# untitled.net
KiCad netlist of a schematic drawn in EAGLE
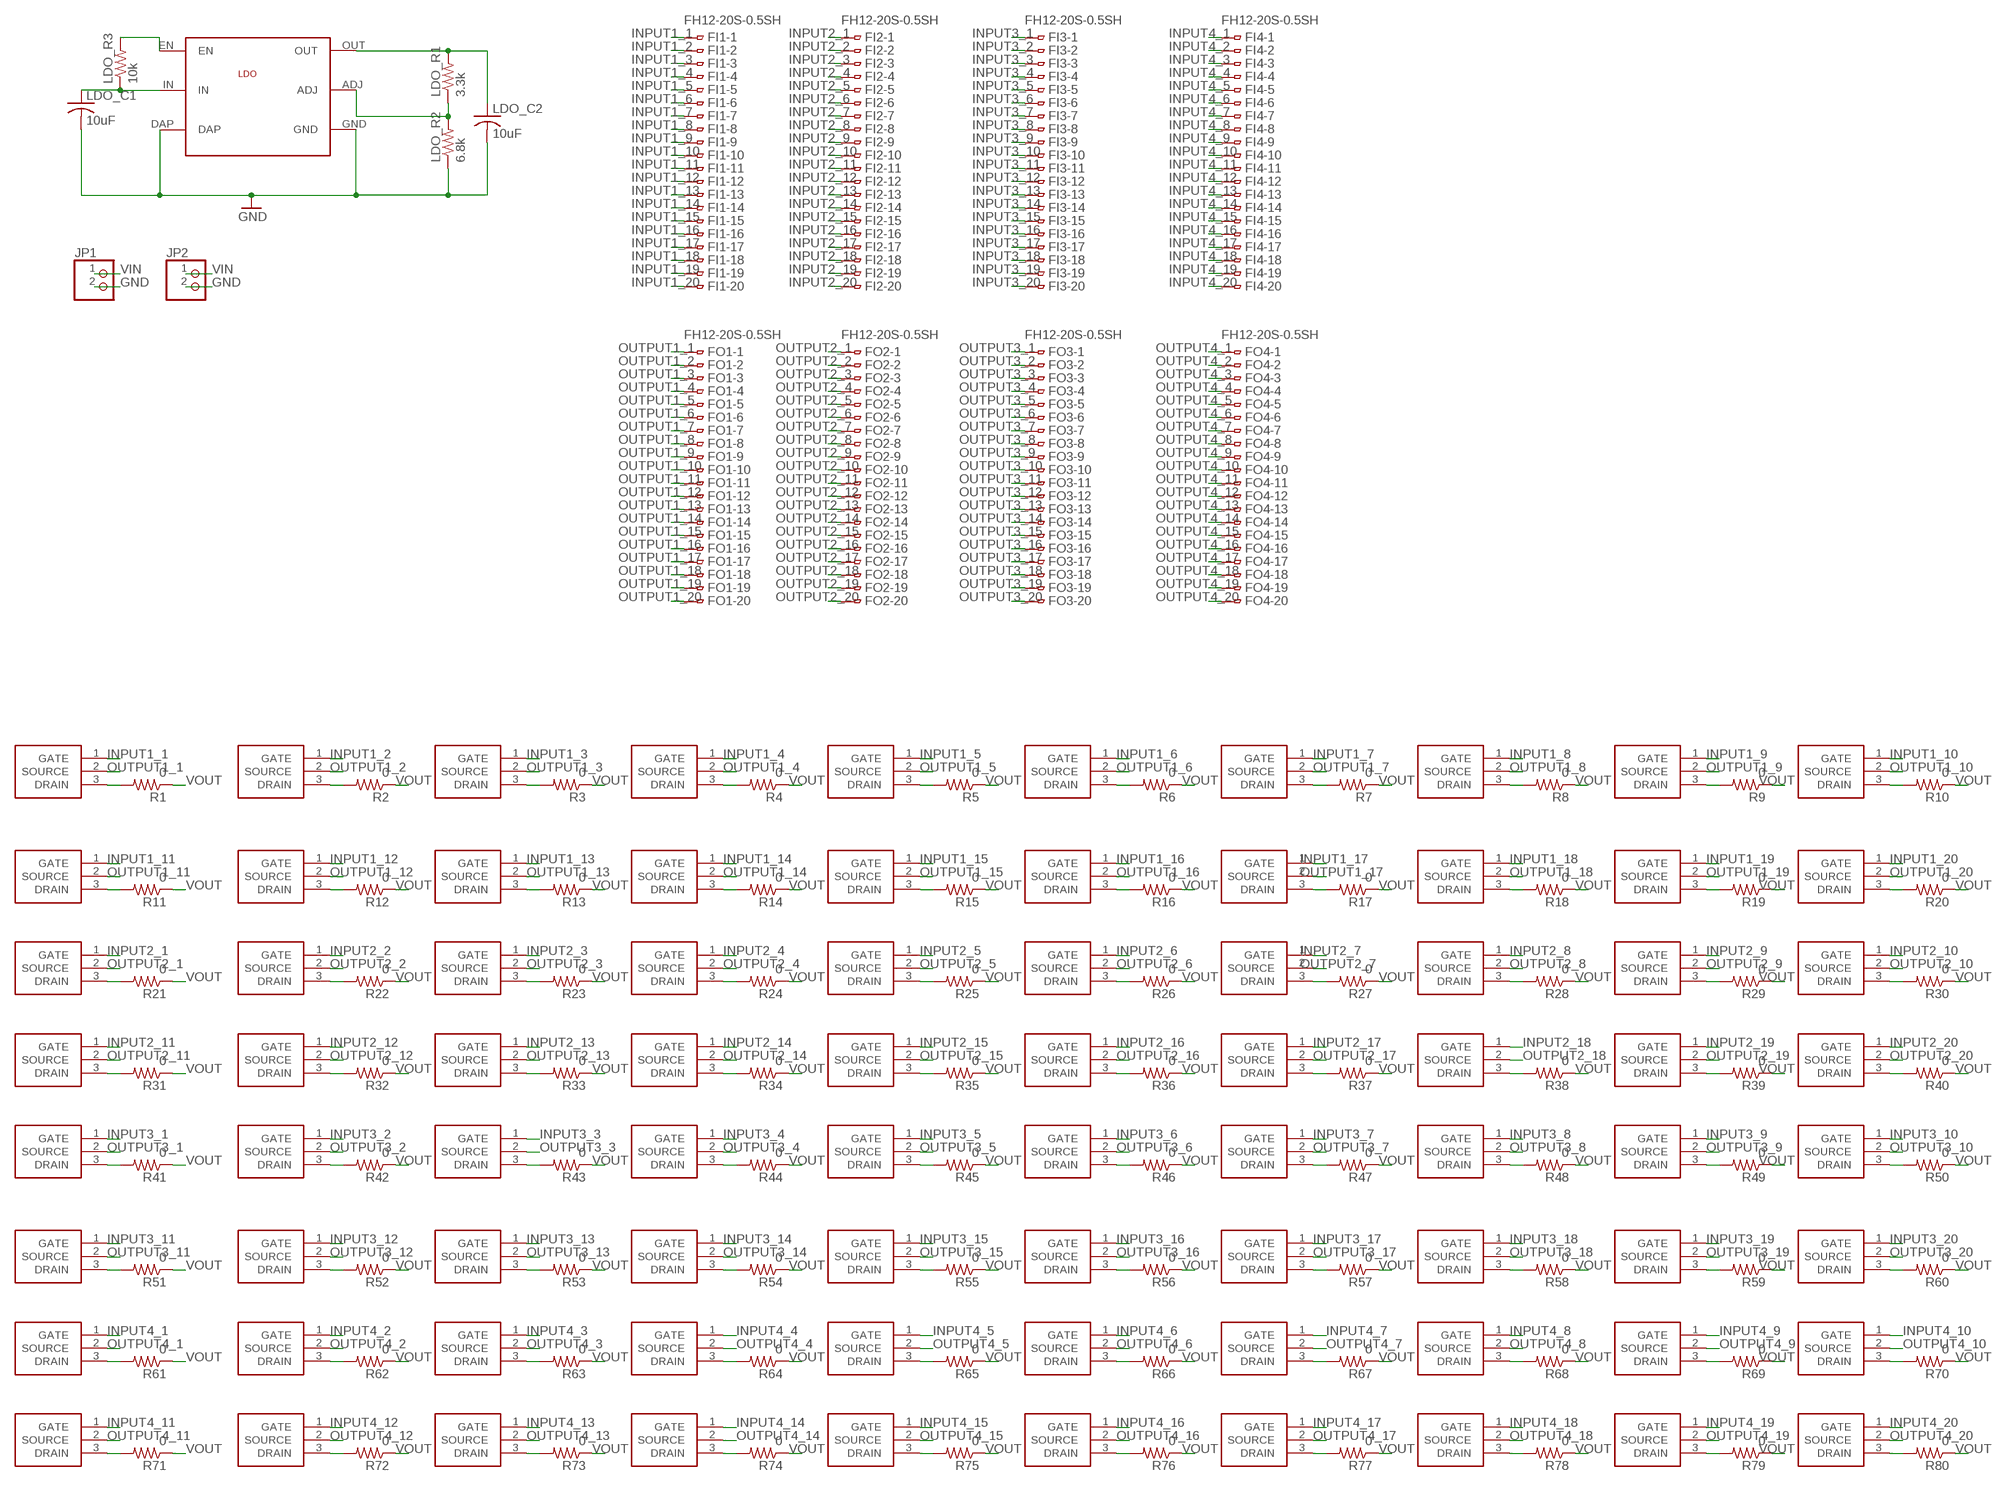
[diagram p0: schematic, sheet 1]

(export (version "E")
  (design (tool "Eeschema 10.0.6"))
  (components
    (comp (ref "FI1")
      (value "FH12-20S-0.5SH")
      (footprint "eagle-import:FH12-20S-0.5SH")
      (fields (field (name "MPN") "FH12-20S-0.5SH(55)"))
      (libsource (lib "eagle-import") (part "FH12-20S-0.5SH"))
    )
    (comp (ref "FI2")
      (value "FH12-20S-0.5SH")
      (footprint "eagle-import:FH12-20S-0.5SH")
      (fields (field (name "MPN") "FH12-20S-0.5SH(55)"))
      (libsource (lib "eagle-import") (part "FH12-20S-0.5SH"))
    )
    (comp (ref "FI3")
      (value "FH12-20S-0.5SH")
      (footprint "eagle-import:FH12-20S-0.5SH")
      (fields (field (name "MPN") "FH12-20S-0.5SH(55)"))
      (libsource (lib "eagle-import") (part "FH12-20S-0.5SH"))
    )
    (comp (ref "FI4")
      (value "FH12-20S-0.5SH")
      (footprint "eagle-import:FH12-20S-0.5SH")
      (fields (field (name "MPN") "FH12-20S-0.5SH(55)"))
      (libsource (lib "eagle-import") (part "FH12-20S-0.5SH"))
    )
    (comp (ref "FO1")
      (value "FH12-20S-0.5SH")
      (footprint "eagle-import:FH12-20S-0.5SH")
      (fields (field (name "MPN") "FH12-20S-0.5SH(55)"))
      (libsource (lib "eagle-import") (part "FH12-20S-0.5SH"))
    )
    (comp (ref "FO2")
      (value "FH12-20S-0.5SH")
      (footprint "eagle-import:FH12-20S-0.5SH")
      (fields (field (name "MPN") "FH12-20S-0.5SH(55)"))
      (libsource (lib "eagle-import") (part "FH12-20S-0.5SH"))
    )
    (comp (ref "FO3")
      (value "FH12-20S-0.5SH")
      (footprint "eagle-import:FH12-20S-0.5SH")
      (fields (field (name "MPN") "FH12-20S-0.5SH(55)"))
      (libsource (lib "eagle-import") (part "FH12-20S-0.5SH"))
    )
    (comp (ref "FO4")
      (value "FH12-20S-0.5SH")
      (footprint "eagle-import:FH12-20S-0.5SH")
      (fields (field (name "MPN") "FH12-20S-0.5SH(55)"))
      (libsource (lib "eagle-import") (part "FH12-20S-0.5SH"))
    )
    (comp (ref "JP1")
      (value "PINHD-1X2")
      (footprint "eagle-import:1X02")
      (libsource (lib "eagle-import") (part "PINHD-1X2"))
    )
    (comp (ref "JP2")
      (value "PINHD-1X2")
      (footprint "eagle-import:1X02")
      (libsource (lib "eagle-import") (part "PINHD-1X2"))
    )
    (comp (ref "LDO")
      (value "LP38501TS_ADJ")
      (footprint "eagle-import:LP38501TS_ADJ")
      (libsource (lib "eagle-import") (part "LP38501TS_ADJ"))
    )
    (comp (ref "LDO_C1")
      (value "10uF")
      (footprint "eagle-import:C0805")
      (libsource (lib "eagle-import") (part "C-USC0805"))
    )
    (comp (ref "LDO_C2")
      (value "10uF")
      (footprint "eagle-import:C0805")
      (libsource (lib "eagle-import") (part "C-USC0805"))
    )
    (comp (ref "LDO_R1")
      (value "3.3k")
      (footprint "eagle-import:R0805")
      (libsource (lib "eagle-import") (part "R-US_R0805"))
    )
    (comp (ref "LDO_R2")
      (value "6.8k")
      (footprint "eagle-import:R0805")
      (libsource (lib "eagle-import") (part "R-US_R0805"))
    )
    (comp (ref "LDO_R3")
      (value "10k")
      (footprint "eagle-import:R0805")
      (libsource (lib "eagle-import") (part "R-US_R0805"))
    )
    (comp (ref "MOS1")
      (value "NX6008NBKNX6008NBK")
      (footprint "eagle-import:SOT95P240X110-3N")
      (libsource (lib "eagle-import") (part "NX6008NBKNX6008NBK"))
    )
    (comp (ref "MOS2")
      (value "NX6008NBKNX6008NBK")
      (footprint "eagle-import:SOT95P240X110-3N")
      (libsource (lib "eagle-import") (part "NX6008NBKNX6008NBK"))
    )
    (comp (ref "MOS3")
      (value "NX6008NBKNX6008NBK")
      (footprint "eagle-import:SOT95P240X110-3N")
      (libsource (lib "eagle-import") (part "NX6008NBKNX6008NBK"))
    )
    (comp (ref "MOS4")
      (value "NX6008NBKNX6008NBK")
      (footprint "eagle-import:SOT95P240X110-3N")
      (libsource (lib "eagle-import") (part "NX6008NBKNX6008NBK"))
    )
    (comp (ref "MOS5")
      (value "NX6008NBKNX6008NBK")
      (footprint "eagle-import:SOT95P240X110-3N")
      (libsource (lib "eagle-import") (part "NX6008NBKNX6008NBK"))
    )
    (comp (ref "MOS6")
      (value "NX6008NBKNX6008NBK")
      (footprint "eagle-import:SOT95P240X110-3N")
      (libsource (lib "eagle-import") (part "NX6008NBKNX6008NBK"))
    )
    (comp (ref "MOS7")
      (value "NX6008NBKNX6008NBK")
      (footprint "eagle-import:SOT95P240X110-3N")
      (libsource (lib "eagle-import") (part "NX6008NBKNX6008NBK"))
    )
    (comp (ref "MOS8")
      (value "NX6008NBKNX6008NBK")
      (footprint "eagle-import:SOT95P240X110-3N")
      (libsource (lib "eagle-import") (part "NX6008NBKNX6008NBK"))
    )
    (comp (ref "MOS9")
      (value "NX6008NBKNX6008NBK")
      (footprint "eagle-import:SOT95P240X110-3N")
      (libsource (lib "eagle-import") (part "NX6008NBKNX6008NBK"))
    )
    (comp (ref "MOS10")
      (value "NX6008NBKNX6008NBK")
      (footprint "eagle-import:SOT95P240X110-3N")
      (libsource (lib "eagle-import") (part "NX6008NBKNX6008NBK"))
    )
    (comp (ref "MOS11")
      (value "NX6008NBKNX6008NBK")
      (footprint "eagle-import:SOT95P240X110-3N")
      (libsource (lib "eagle-import") (part "NX6008NBKNX6008NBK"))
    )
    (comp (ref "MOS12")
      (value "NX6008NBKNX6008NBK")
      (footprint "eagle-import:SOT95P240X110-3N")
      (libsource (lib "eagle-import") (part "NX6008NBKNX6008NBK"))
    )
    (comp (ref "MOS13")
      (value "NX6008NBKNX6008NBK")
      (footprint "eagle-import:SOT95P240X110-3N")
      (libsource (lib "eagle-import") (part "NX6008NBKNX6008NBK"))
    )
    (comp (ref "MOS14")
      (value "NX6008NBKNX6008NBK")
      (footprint "eagle-import:SOT95P240X110-3N")
      (libsource (lib "eagle-import") (part "NX6008NBKNX6008NBK"))
    )
    (comp (ref "MOS15")
      (value "NX6008NBKNX6008NBK")
      (footprint "eagle-import:SOT95P240X110-3N")
      (libsource (lib "eagle-import") (part "NX6008NBKNX6008NBK"))
    )
    (comp (ref "MOS16")
      (value "NX6008NBKNX6008NBK")
      (footprint "eagle-import:SOT95P240X110-3N")
      (libsource (lib "eagle-import") (part "NX6008NBKNX6008NBK"))
    )
    (comp (ref "MOS17")
      (value "NX6008NBKNX6008NBK")
      (footprint "eagle-import:SOT95P240X110-3N")
      (libsource (lib "eagle-import") (part "NX6008NBKNX6008NBK"))
    )
    (comp (ref "MOS18")
      (value "NX6008NBKNX6008NBK")
      (footprint "eagle-import:SOT95P240X110-3N")
      (libsource (lib "eagle-import") (part "NX6008NBKNX6008NBK"))
    )
    (comp (ref "MOS19")
      (value "NX6008NBKNX6008NBK")
      (footprint "eagle-import:SOT95P240X110-3N")
      (libsource (lib "eagle-import") (part "NX6008NBKNX6008NBK"))
    )
    (comp (ref "MOS20")
      (value "NX6008NBKNX6008NBK")
      (footprint "eagle-import:SOT95P240X110-3N")
      (libsource (lib "eagle-import") (part "NX6008NBKNX6008NBK"))
    )
    (comp (ref "MOS21")
      (value "NX6008NBKNX6008NBK")
      (footprint "eagle-import:SOT95P240X110-3N")
      (libsource (lib "eagle-import") (part "NX6008NBKNX6008NBK"))
    )
    (comp (ref "MOS22")
      (value "NX6008NBKNX6008NBK")
      (footprint "eagle-import:SOT95P240X110-3N")
      (libsource (lib "eagle-import") (part "NX6008NBKNX6008NBK"))
    )
    (comp (ref "MOS23")
      (value "NX6008NBKNX6008NBK")
      (footprint "eagle-import:SOT95P240X110-3N")
      (libsource (lib "eagle-import") (part "NX6008NBKNX6008NBK"))
    )
    (comp (ref "MOS24")
      (value "NX6008NBKNX6008NBK")
      (footprint "eagle-import:SOT95P240X110-3N")
      (libsource (lib "eagle-import") (part "NX6008NBKNX6008NBK"))
    )
    (comp (ref "MOS25")
      (value "NX6008NBKNX6008NBK")
      (footprint "eagle-import:SOT95P240X110-3N")
      (libsource (lib "eagle-import") (part "NX6008NBKNX6008NBK"))
    )
    (comp (ref "MOS26")
      (value "NX6008NBKNX6008NBK")
      (footprint "eagle-import:SOT95P240X110-3N")
      (libsource (lib "eagle-import") (part "NX6008NBKNX6008NBK"))
    )
    (comp (ref "MOS27")
      (value "NX6008NBKNX6008NBK")
      (footprint "eagle-import:SOT95P240X110-3N")
      (libsource (lib "eagle-import") (part "NX6008NBKNX6008NBK"))
    )
    (comp (ref "MOS28")
      (value "NX6008NBKNX6008NBK")
      (footprint "eagle-import:SOT95P240X110-3N")
      (libsource (lib "eagle-import") (part "NX6008NBKNX6008NBK"))
    )
    (comp (ref "MOS29")
      (value "NX6008NBKNX6008NBK")
      (footprint "eagle-import:SOT95P240X110-3N")
      (libsource (lib "eagle-import") (part "NX6008NBKNX6008NBK"))
    )
    (comp (ref "MOS30")
      (value "NX6008NBKNX6008NBK")
      (footprint "eagle-import:SOT95P240X110-3N")
      (libsource (lib "eagle-import") (part "NX6008NBKNX6008NBK"))
    )
    (comp (ref "MOS31")
      (value "NX6008NBKNX6008NBK")
      (footprint "eagle-import:SOT95P240X110-3N")
      (libsource (lib "eagle-import") (part "NX6008NBKNX6008NBK"))
    )
    (comp (ref "MOS32")
      (value "NX6008NBKNX6008NBK")
      (footprint "eagle-import:SOT95P240X110-3N")
      (libsource (lib "eagle-import") (part "NX6008NBKNX6008NBK"))
    )
    (comp (ref "MOS33")
      (value "NX6008NBKNX6008NBK")
      (footprint "eagle-import:SOT95P240X110-3N")
      (libsource (lib "eagle-import") (part "NX6008NBKNX6008NBK"))
    )
    (comp (ref "MOS34")
      (value "NX6008NBKNX6008NBK")
      (footprint "eagle-import:SOT95P240X110-3N")
      (libsource (lib "eagle-import") (part "NX6008NBKNX6008NBK"))
    )
    (comp (ref "MOS35")
      (value "NX6008NBKNX6008NBK")
      (footprint "eagle-import:SOT95P240X110-3N")
      (libsource (lib "eagle-import") (part "NX6008NBKNX6008NBK"))
    )
    (comp (ref "MOS36")
      (value "NX6008NBKNX6008NBK")
      (footprint "eagle-import:SOT95P240X110-3N")
      (libsource (lib "eagle-import") (part "NX6008NBKNX6008NBK"))
    )
    (comp (ref "MOS37")
      (value "NX6008NBKNX6008NBK")
      (footprint "eagle-import:SOT95P240X110-3N")
      (libsource (lib "eagle-import") (part "NX6008NBKNX6008NBK"))
    )
    (comp (ref "MOS38")
      (value "NX6008NBKNX6008NBK")
      (footprint "eagle-import:SOT95P240X110-3N")
      (libsource (lib "eagle-import") (part "NX6008NBKNX6008NBK"))
    )
    (comp (ref "MOS39")
      (value "NX6008NBKNX6008NBK")
      (footprint "eagle-import:SOT95P240X110-3N")
      (libsource (lib "eagle-import") (part "NX6008NBKNX6008NBK"))
    )
    (comp (ref "MOS40")
      (value "NX6008NBKNX6008NBK")
      (footprint "eagle-import:SOT95P240X110-3N")
      (libsource (lib "eagle-import") (part "NX6008NBKNX6008NBK"))
    )
    (comp (ref "MOS41")
      (value "NX6008NBKNX6008NBK")
      (footprint "eagle-import:SOT95P240X110-3N")
      (libsource (lib "eagle-import") (part "NX6008NBKNX6008NBK"))
    )
    (comp (ref "MOS42")
      (value "NX6008NBKNX6008NBK")
      (footprint "eagle-import:SOT95P240X110-3N")
      (libsource (lib "eagle-import") (part "NX6008NBKNX6008NBK"))
    )
    (comp (ref "MOS43")
      (value "NX6008NBKNX6008NBK")
      (footprint "eagle-import:SOT95P240X110-3N")
      (libsource (lib "eagle-import") (part "NX6008NBKNX6008NBK"))
    )
    (comp (ref "MOS44")
      (value "NX6008NBKNX6008NBK")
      (footprint "eagle-import:SOT95P240X110-3N")
      (libsource (lib "eagle-import") (part "NX6008NBKNX6008NBK"))
    )
    (comp (ref "MOS45")
      (value "NX6008NBKNX6008NBK")
      (footprint "eagle-import:SOT95P240X110-3N")
      (libsource (lib "eagle-import") (part "NX6008NBKNX6008NBK"))
    )
    (comp (ref "MOS46")
      (value "NX6008NBKNX6008NBK")
      (footprint "eagle-import:SOT95P240X110-3N")
      (libsource (lib "eagle-import") (part "NX6008NBKNX6008NBK"))
    )
    (comp (ref "MOS47")
      (value "NX6008NBKNX6008NBK")
      (footprint "eagle-import:SOT95P240X110-3N")
      (libsource (lib "eagle-import") (part "NX6008NBKNX6008NBK"))
    )
    (comp (ref "MOS48")
      (value "NX6008NBKNX6008NBK")
      (footprint "eagle-import:SOT95P240X110-3N")
      (libsource (lib "eagle-import") (part "NX6008NBKNX6008NBK"))
    )
    (comp (ref "MOS49")
      (value "NX6008NBKNX6008NBK")
      (footprint "eagle-import:SOT95P240X110-3N")
      (libsource (lib "eagle-import") (part "NX6008NBKNX6008NBK"))
    )
    (comp (ref "MOS50")
      (value "NX6008NBKNX6008NBK")
      (footprint "eagle-import:SOT95P240X110-3N")
      (libsource (lib "eagle-import") (part "NX6008NBKNX6008NBK"))
    )
    (comp (ref "MOS51")
      (value "NX6008NBKNX6008NBK")
      (footprint "eagle-import:SOT95P240X110-3N")
      (libsource (lib "eagle-import") (part "NX6008NBKNX6008NBK"))
    )
    (comp (ref "MOS52")
      (value "NX6008NBKNX6008NBK")
      (footprint "eagle-import:SOT95P240X110-3N")
      (libsource (lib "eagle-import") (part "NX6008NBKNX6008NBK"))
    )
    (comp (ref "MOS53")
      (value "NX6008NBKNX6008NBK")
      (footprint "eagle-import:SOT95P240X110-3N")
      (libsource (lib "eagle-import") (part "NX6008NBKNX6008NBK"))
    )
    (comp (ref "MOS54")
      (value "NX6008NBKNX6008NBK")
      (footprint "eagle-import:SOT95P240X110-3N")
      (libsource (lib "eagle-import") (part "NX6008NBKNX6008NBK"))
    )
    (comp (ref "MOS55")
      (value "NX6008NBKNX6008NBK")
      (footprint "eagle-import:SOT95P240X110-3N")
      (libsource (lib "eagle-import") (part "NX6008NBKNX6008NBK"))
    )
    (comp (ref "MOS56")
      (value "NX6008NBKNX6008NBK")
      (footprint "eagle-import:SOT95P240X110-3N")
      (libsource (lib "eagle-import") (part "NX6008NBKNX6008NBK"))
    )
    (comp (ref "MOS57")
      (value "NX6008NBKNX6008NBK")
      (footprint "eagle-import:SOT95P240X110-3N")
      (libsource (lib "eagle-import") (part "NX6008NBKNX6008NBK"))
    )
    (comp (ref "MOS58")
      (value "NX6008NBKNX6008NBK")
      (footprint "eagle-import:SOT95P240X110-3N")
      (libsource (lib "eagle-import") (part "NX6008NBKNX6008NBK"))
    )
    (comp (ref "MOS59")
      (value "NX6008NBKNX6008NBK")
      (footprint "eagle-import:SOT95P240X110-3N")
      (libsource (lib "eagle-import") (part "NX6008NBKNX6008NBK"))
    )
    (comp (ref "MOS60")
      (value "NX6008NBKNX6008NBK")
      (footprint "eagle-import:SOT95P240X110-3N")
      (libsource (lib "eagle-import") (part "NX6008NBKNX6008NBK"))
    )
    (comp (ref "MOS61")
      (value "NX6008NBKNX6008NBK")
      (footprint "eagle-import:SOT95P240X110-3N")
      (libsource (lib "eagle-import") (part "NX6008NBKNX6008NBK"))
    )
    (comp (ref "MOS62")
      (value "NX6008NBKNX6008NBK")
      (footprint "eagle-import:SOT95P240X110-3N")
      (libsource (lib "eagle-import") (part "NX6008NBKNX6008NBK"))
    )
    (comp (ref "MOS63")
      (value "NX6008NBKNX6008NBK")
      (footprint "eagle-import:SOT95P240X110-3N")
      (libsource (lib "eagle-import") (part "NX6008NBKNX6008NBK"))
    )
    (comp (ref "MOS64")
      (value "NX6008NBKNX6008NBK")
      (footprint "eagle-import:SOT95P240X110-3N")
      (libsource (lib "eagle-import") (part "NX6008NBKNX6008NBK"))
    )
    (comp (ref "MOS65")
      (value "NX6008NBKNX6008NBK")
      (footprint "eagle-import:SOT95P240X110-3N")
      (libsource (lib "eagle-import") (part "NX6008NBKNX6008NBK"))
    )
    (comp (ref "MOS66")
      (value "NX6008NBKNX6008NBK")
      (footprint "eagle-import:SOT95P240X110-3N")
      (libsource (lib "eagle-import") (part "NX6008NBKNX6008NBK"))
    )
    (comp (ref "MOS67")
      (value "NX6008NBKNX6008NBK")
      (footprint "eagle-import:SOT95P240X110-3N")
      (libsource (lib "eagle-import") (part "NX6008NBKNX6008NBK"))
    )
    (comp (ref "MOS68")
      (value "NX6008NBKNX6008NBK")
      (footprint "eagle-import:SOT95P240X110-3N")
      (libsource (lib "eagle-import") (part "NX6008NBKNX6008NBK"))
    )
    (comp (ref "MOS69")
      (value "NX6008NBKNX6008NBK")
      (footprint "eagle-import:SOT95P240X110-3N")
      (libsource (lib "eagle-import") (part "NX6008NBKNX6008NBK"))
    )
    (comp (ref "MOS70")
      (value "NX6008NBKNX6008NBK")
      (footprint "eagle-import:SOT95P240X110-3N")
      (libsource (lib "eagle-import") (part "NX6008NBKNX6008NBK"))
    )
    (comp (ref "MOS71")
      (value "NX6008NBKNX6008NBK")
      (footprint "eagle-import:SOT95P240X110-3N")
      (libsource (lib "eagle-import") (part "NX6008NBKNX6008NBK"))
    )
    (comp (ref "MOS72")
      (value "NX6008NBKNX6008NBK")
      (footprint "eagle-import:SOT95P240X110-3N")
      (libsource (lib "eagle-import") (part "NX6008NBKNX6008NBK"))
    )
    (comp (ref "MOS73")
      (value "NX6008NBKNX6008NBK")
      (footprint "eagle-import:SOT95P240X110-3N")
      (libsource (lib "eagle-import") (part "NX6008NBKNX6008NBK"))
    )
    (comp (ref "MOS74")
      (value "NX6008NBKNX6008NBK")
      (footprint "eagle-import:SOT95P240X110-3N")
      (libsource (lib "eagle-import") (part "NX6008NBKNX6008NBK"))
    )
    (comp (ref "MOS75")
      (value "NX6008NBKNX6008NBK")
      (footprint "eagle-import:SOT95P240X110-3N")
      (libsource (lib "eagle-import") (part "NX6008NBKNX6008NBK"))
    )
    (comp (ref "MOS76")
      (value "NX6008NBKNX6008NBK")
      (footprint "eagle-import:SOT95P240X110-3N")
      (libsource (lib "eagle-import") (part "NX6008NBKNX6008NBK"))
    )
    (comp (ref "MOS77")
      (value "NX6008NBKNX6008NBK")
      (footprint "eagle-import:SOT95P240X110-3N")
      (libsource (lib "eagle-import") (part "NX6008NBKNX6008NBK"))
    )
    (comp (ref "MOS78")
      (value "NX6008NBKNX6008NBK")
      (footprint "eagle-import:SOT95P240X110-3N")
      (libsource (lib "eagle-import") (part "NX6008NBKNX6008NBK"))
    )
    (comp (ref "MOS79")
      (value "NX6008NBKNX6008NBK")
      (footprint "eagle-import:SOT95P240X110-3N")
      (libsource (lib "eagle-import") (part "NX6008NBKNX6008NBK"))
    )
    (comp (ref "MOS80")
      (value "NX6008NBKNX6008NBK")
      (footprint "eagle-import:SOT95P240X110-3N")
      (libsource (lib "eagle-import") (part "NX6008NBKNX6008NBK"))
    )
    (comp (ref "R1")
      (value "0")
      (footprint "eagle-import:R0805")
      (libsource (lib "eagle-import") (part "R-US_R0805"))
    )
    (comp (ref "R2")
      (value "0")
      (footprint "eagle-import:R0805")
      (libsource (lib "eagle-import") (part "R-US_R0805"))
    )
    (comp (ref "R3")
      (value "0")
      (footprint "eagle-import:R0805")
      (libsource (lib "eagle-import") (part "R-US_R0805"))
    )
    (comp (ref "R4")
      (value "0")
      (footprint "eagle-import:R0805")
      (libsource (lib "eagle-import") (part "R-US_R0805"))
    )
    (comp (ref "R5")
      (value "0")
      (footprint "eagle-import:R0805")
      (libsource (lib "eagle-import") (part "R-US_R0805"))
    )
    (comp (ref "R6")
      (value "0")
      (footprint "eagle-import:R0805")
      (libsource (lib "eagle-import") (part "R-US_R0805"))
    )
    (comp (ref "R7")
      (value "0")
      (footprint "eagle-import:R0805")
      (libsource (lib "eagle-import") (part "R-US_R0805"))
    )
    (comp (ref "R8")
      (value "0")
      (footprint "eagle-import:R0805")
      (libsource (lib "eagle-import") (part "R-US_R0805"))
    )
    (comp (ref "R9")
      (value "0")
      (footprint "eagle-import:R0805")
      (libsource (lib "eagle-import") (part "R-US_R0805"))
    )
    (comp (ref "R10")
      (value "0")
      (footprint "eagle-import:R0805")
      (libsource (lib "eagle-import") (part "R-US_R0805"))
    )
    (comp (ref "R11")
      (value "0")
      (footprint "eagle-import:R0805")
      (libsource (lib "eagle-import") (part "R-US_R0805"))
    )
    (comp (ref "R12")
      (value "0")
      (footprint "eagle-import:R0805")
      (libsource (lib "eagle-import") (part "R-US_R0805"))
    )
    (comp (ref "R13")
      (value "0")
      (footprint "eagle-import:R0805")
      (libsource (lib "eagle-import") (part "R-US_R0805"))
    )
    (comp (ref "R14")
      (value "0")
      (footprint "eagle-import:R0805")
      (libsource (lib "eagle-import") (part "R-US_R0805"))
    )
    (comp (ref "R15")
      (value "0")
      (footprint "eagle-import:R0805")
      (libsource (lib "eagle-import") (part "R-US_R0805"))
    )
    (comp (ref "R16")
      (value "0")
      (footprint "eagle-import:R0805")
      (libsource (lib "eagle-import") (part "R-US_R0805"))
    )
    (comp (ref "R17")
      (value "0")
      (footprint "eagle-import:R0805")
      (libsource (lib "eagle-import") (part "R-US_R0805"))
    )
    (comp (ref "R18")
      (value "0")
      (footprint "eagle-import:R0805")
      (libsource (lib "eagle-import") (part "R-US_R0805"))
    )
    (comp (ref "R19")
      (value "0")
      (footprint "eagle-import:R0805")
      (libsource (lib "eagle-import") (part "R-US_R0805"))
    )
    (comp (ref "R20")
      (value "0")
      (footprint "eagle-import:R0805")
      (libsource (lib "eagle-import") (part "R-US_R0805"))
    )
    (comp (ref "R21")
      (value "0")
      (footprint "eagle-import:R0805")
      (libsource (lib "eagle-import") (part "R-US_R0805"))
    )
    (comp (ref "R22")
      (value "0")
      (footprint "eagle-import:R0805")
      (libsource (lib "eagle-import") (part "R-US_R0805"))
    )
    (comp (ref "R23")
      (value "0")
      (footprint "eagle-import:R0805")
      (libsource (lib "eagle-import") (part "R-US_R0805"))
    )
    (comp (ref "R24")
      (value "0")
      (footprint "eagle-import:R0805")
      (libsource (lib "eagle-import") (part "R-US_R0805"))
    )
    (comp (ref "R25")
      (value "0")
      (footprint "eagle-import:R0805")
      (libsource (lib "eagle-import") (part "R-US_R0805"))
    )
    (comp (ref "R26")
      (value "0")
      (footprint "eagle-import:R0805")
      (libsource (lib "eagle-import") (part "R-US_R0805"))
    )
    (comp (ref "R27")
      (value "0")
      (footprint "eagle-import:R0805")
      (libsource (lib "eagle-import") (part "R-US_R0805"))
    )
    (comp (ref "R28")
      (value "0")
      (footprint "eagle-import:R0805")
      (libsource (lib "eagle-import") (part "R-US_R0805"))
    )
    (comp (ref "R29")
      (value "0")
      (footprint "eagle-import:R0805")
      (libsource (lib "eagle-import") (part "R-US_R0805"))
    )
    (comp (ref "R30")
      (value "0")
      (footprint "eagle-import:R0805")
      (libsource (lib "eagle-import") (part "R-US_R0805"))
    )
    (comp (ref "R31")
      (value "0")
      (footprint "eagle-import:R0805")
      (libsource (lib "eagle-import") (part "R-US_R0805"))
    )
    (comp (ref "R32")
      (value "0")
      (footprint "eagle-import:R0805")
      (libsource (lib "eagle-import") (part "R-US_R0805"))
    )
    (comp (ref "R33")
      (value "0")
      (footprint "eagle-import:R0805")
      (libsource (lib "eagle-import") (part "R-US_R0805"))
    )
    (comp (ref "R34")
      (value "0")
      (footprint "eagle-import:R0805")
      (libsource (lib "eagle-import") (part "R-US_R0805"))
    )
    (comp (ref "R35")
      (value "0")
      (footprint "eagle-import:R0805")
      (libsource (lib "eagle-import") (part "R-US_R0805"))
    )
    (comp (ref "R36")
      (value "0")
      (footprint "eagle-import:R0805")
      (libsource (lib "eagle-import") (part "R-US_R0805"))
    )
    (comp (ref "R37")
      (value "0")
      (footprint "eagle-import:R0805")
      (libsource (lib "eagle-import") (part "R-US_R0805"))
    )
    (comp (ref "R38")
      (value "0")
      (footprint "eagle-import:R0805")
      (libsource (lib "eagle-import") (part "R-US_R0805"))
    )
    (comp (ref "R39")
      (value "0")
      (footprint "eagle-import:R0805")
      (libsource (lib "eagle-import") (part "R-US_R0805"))
    )
    (comp (ref "R40")
      (value "0")
      (footprint "eagle-import:R0805")
      (libsource (lib "eagle-import") (part "R-US_R0805"))
    )
    (comp (ref "R41")
      (value "0")
      (footprint "eagle-import:R0805")
      (libsource (lib "eagle-import") (part "R-US_R0805"))
    )
    (comp (ref "R42")
      (value "0")
      (footprint "eagle-import:R0805")
      (libsource (lib "eagle-import") (part "R-US_R0805"))
    )
    (comp (ref "R43")
      (value "0")
      (footprint "eagle-import:R0805")
      (libsource (lib "eagle-import") (part "R-US_R0805"))
    )
    (comp (ref "R44")
      (value "0")
      (footprint "eagle-import:R0805")
      (libsource (lib "eagle-import") (part "R-US_R0805"))
    )
    (comp (ref "R45")
      (value "0")
      (footprint "eagle-import:R0805")
      (libsource (lib "eagle-import") (part "R-US_R0805"))
    )
    (comp (ref "R46")
      (value "0")
      (footprint "eagle-import:R0805")
      (libsource (lib "eagle-import") (part "R-US_R0805"))
    )
    (comp (ref "R47")
      (value "0")
      (footprint "eagle-import:R0805")
      (libsource (lib "eagle-import") (part "R-US_R0805"))
    )
    (comp (ref "R48")
      (value "0")
      (footprint "eagle-import:R0805")
      (libsource (lib "eagle-import") (part "R-US_R0805"))
    )
    (comp (ref "R49")
      (value "0")
      (footprint "eagle-import:R0805")
      (libsource (lib "eagle-import") (part "R-US_R0805"))
    )
    (comp (ref "R50")
      (value "0")
      (footprint "eagle-import:R0805")
      (libsource (lib "eagle-import") (part "R-US_R0805"))
    )
    (comp (ref "R51")
      (value "0")
      (footprint "eagle-import:R0805")
      (libsource (lib "eagle-import") (part "R-US_R0805"))
    )
    (comp (ref "R52")
      (value "0")
      (footprint "eagle-import:R0805")
      (libsource (lib "eagle-import") (part "R-US_R0805"))
    )
    (comp (ref "R53")
      (value "0")
      (footprint "eagle-import:R0805")
      (libsource (lib "eagle-import") (part "R-US_R0805"))
    )
    (comp (ref "R54")
      (value "0")
      (footprint "eagle-import:R0805")
      (libsource (lib "eagle-import") (part "R-US_R0805"))
    )
    (comp (ref "R55")
      (value "0")
      (footprint "eagle-import:R0805")
      (libsource (lib "eagle-import") (part "R-US_R0805"))
    )
    (comp (ref "R56")
      (value "0")
      (footprint "eagle-import:R0805")
      (libsource (lib "eagle-import") (part "R-US_R0805"))
    )
    (comp (ref "R57")
      (value "0")
      (footprint "eagle-import:R0805")
      (libsource (lib "eagle-import") (part "R-US_R0805"))
    )
    (comp (ref "R58")
      (value "0")
      (footprint "eagle-import:R0805")
      (libsource (lib "eagle-import") (part "R-US_R0805"))
    )
    (comp (ref "R59")
      (value "0")
      (footprint "eagle-import:R0805")
      (libsource (lib "eagle-import") (part "R-US_R0805"))
    )
    (comp (ref "R60")
      (value "0")
      (footprint "eagle-import:R0805")
      (libsource (lib "eagle-import") (part "R-US_R0805"))
    )
    (comp (ref "R61")
      (value "0")
      (footprint "eagle-import:R0805")
      (libsource (lib "eagle-import") (part "R-US_R0805"))
    )
    (comp (ref "R62")
      (value "0")
      (footprint "eagle-import:R0805")
      (libsource (lib "eagle-import") (part "R-US_R0805"))
    )
    (comp (ref "R63")
      (value "0")
      (footprint "eagle-import:R0805")
      (libsource (lib "eagle-import") (part "R-US_R0805"))
    )
    (comp (ref "R64")
      (value "0")
      (footprint "eagle-import:R0805")
      (libsource (lib "eagle-import") (part "R-US_R0805"))
    )
    (comp (ref "R65")
      (value "0")
      (footprint "eagle-import:R0805")
      (libsource (lib "eagle-import") (part "R-US_R0805"))
    )
    (comp (ref "R66")
      (value "0")
      (footprint "eagle-import:R0805")
      (libsource (lib "eagle-import") (part "R-US_R0805"))
    )
    (comp (ref "R67")
      (value "0")
      (footprint "eagle-import:R0805")
      (libsource (lib "eagle-import") (part "R-US_R0805"))
    )
    (comp (ref "R68")
      (value "0")
      (footprint "eagle-import:R0805")
      (libsource (lib "eagle-import") (part "R-US_R0805"))
    )
    (comp (ref "R69")
      (value "0")
      (footprint "eagle-import:R0805")
      (libsource (lib "eagle-import") (part "R-US_R0805"))
    )
    (comp (ref "R70")
      (value "0")
      (footprint "eagle-import:R0805")
      (libsource (lib "eagle-import") (part "R-US_R0805"))
    )
    (comp (ref "R71")
      (value "0")
      (footprint "eagle-import:R0805")
      (libsource (lib "eagle-import") (part "R-US_R0805"))
    )
    (comp (ref "R72")
      (value "0")
      (footprint "eagle-import:R0805")
      (libsource (lib "eagle-import") (part "R-US_R0805"))
    )
    (comp (ref "R73")
      (value "0")
      (footprint "eagle-import:R0805")
      (libsource (lib "eagle-import") (part "R-US_R0805"))
    )
    (comp (ref "R74")
      (value "0")
      (footprint "eagle-import:R0805")
      (libsource (lib "eagle-import") (part "R-US_R0805"))
    )
    (comp (ref "R75")
      (value "0")
      (footprint "eagle-import:R0805")
      (libsource (lib "eagle-import") (part "R-US_R0805"))
    )
    (comp (ref "R76")
      (value "0")
      (footprint "eagle-import:R0805")
      (libsource (lib "eagle-import") (part "R-US_R0805"))
    )
    (comp (ref "R77")
      (value "0")
      (footprint "eagle-import:R0805")
      (libsource (lib "eagle-import") (part "R-US_R0805"))
    )
    (comp (ref "R78")
      (value "0")
      (footprint "eagle-import:R0805")
      (libsource (lib "eagle-import") (part "R-US_R0805"))
    )
    (comp (ref "R79")
      (value "0")
      (footprint "eagle-import:R0805")
      (libsource (lib "eagle-import") (part "R-US_R0805"))
    )
    (comp (ref "R80")
      (value "0")
      (footprint "eagle-import:R0805")
      (libsource (lib "eagle-import") (part "R-US_R0805"))
    )
  )
  (nets
    (net (code "1") (name "/INPUT1_1") (class "Default")
      (node (ref "FI1") (pin "1") (pinfunction "1_1") (pintype "passive"))
      (node (ref "MOS1") (pin "1") (pinfunction "GATE_1") (pintype "bidirectional"))
    )
    (net (code "2") (name "/INPUT1_2") (class "Default")
      (node (ref "FI1") (pin "2") (pinfunction "1_2") (pintype "passive"))
      (node (ref "MOS2") (pin "1") (pinfunction "GATE_1") (pintype "bidirectional"))
    )
    (net (code "3") (name "/INPUT1_3") (class "Default")
      (node (ref "FI1") (pin "3") (pinfunction "1_3") (pintype "passive"))
      (node (ref "MOS3") (pin "1") (pinfunction "GATE_1") (pintype "bidirectional"))
    )
    (net (code "4") (name "/INPUT1_4") (class "Default")
      (node (ref "FI1") (pin "4") (pinfunction "1_4") (pintype "passive"))
      (node (ref "MOS4") (pin "1") (pinfunction "GATE_1") (pintype "bidirectional"))
    )
    (net (code "5") (name "/INPUT1_5") (class "Default")
      (node (ref "FI1") (pin "5") (pinfunction "1_5") (pintype "passive"))
      (node (ref "MOS5") (pin "1") (pinfunction "GATE_1") (pintype "bidirectional"))
    )
    (net (code "6") (name "/INPUT1_6") (class "Default")
      (node (ref "FI1") (pin "6") (pinfunction "1_6") (pintype "passive"))
      (node (ref "MOS6") (pin "1") (pinfunction "GATE_1") (pintype "bidirectional"))
    )
    (net (code "7") (name "/INPUT1_7") (class "Default")
      (node (ref "FI1") (pin "7") (pinfunction "1_7") (pintype "passive"))
      (node (ref "MOS7") (pin "1") (pinfunction "GATE_1") (pintype "bidirectional"))
    )
    (net (code "8") (name "/INPUT1_8") (class "Default")
      (node (ref "FI1") (pin "8") (pinfunction "1_8") (pintype "passive"))
      (node (ref "MOS8") (pin "1") (pinfunction "GATE_1") (pintype "bidirectional"))
    )
    (net (code "9") (name "/INPUT1_9") (class "Default")
      (node (ref "FI1") (pin "9") (pinfunction "1_9") (pintype "passive"))
      (node (ref "MOS9") (pin "1") (pinfunction "GATE_1") (pintype "bidirectional"))
    )
    (net (code "10") (name "/INPUT1_10") (class "Default")
      (node (ref "FI1") (pin "10") (pinfunction "1_10") (pintype "passive"))
      (node (ref "MOS10") (pin "1") (pinfunction "GATE_1") (pintype "bidirectional"))
    )
    (net (code "11") (name "/INPUT1_11") (class "Default")
      (node (ref "FI1") (pin "11") (pinfunction "1_11") (pintype "passive"))
      (node (ref "MOS11") (pin "1") (pinfunction "GATE_1") (pintype "bidirectional"))
    )
    (net (code "12") (name "/INPUT1_12") (class "Default")
      (node (ref "FI1") (pin "12") (pinfunction "1_12") (pintype "passive"))
      (node (ref "MOS12") (pin "1") (pinfunction "GATE_1") (pintype "bidirectional"))
    )
    (net (code "13") (name "/INPUT1_13") (class "Default")
      (node (ref "FI1") (pin "13") (pinfunction "1_13") (pintype "passive"))
      (node (ref "MOS13") (pin "1") (pinfunction "GATE_1") (pintype "bidirectional"))
    )
    (net (code "14") (name "/INPUT1_14") (class "Default")
      (node (ref "FI1") (pin "14") (pinfunction "1_14") (pintype "passive"))
      (node (ref "MOS14") (pin "1") (pinfunction "GATE_1") (pintype "bidirectional"))
    )
    (net (code "15") (name "/INPUT1_15") (class "Default")
      (node (ref "FI1") (pin "15") (pinfunction "1_15") (pintype "passive"))
      (node (ref "MOS15") (pin "1") (pinfunction "GATE_1") (pintype "bidirectional"))
    )
    (net (code "16") (name "/INPUT1_16") (class "Default")
      (node (ref "FI1") (pin "16") (pinfunction "1_16") (pintype "passive"))
      (node (ref "MOS16") (pin "1") (pinfunction "GATE_1") (pintype "bidirectional"))
    )
    (net (code "17") (name "/INPUT1_17") (class "Default")
      (node (ref "FI1") (pin "17") (pinfunction "1_17") (pintype "passive"))
      (node (ref "MOS17") (pin "1") (pinfunction "GATE_1") (pintype "bidirectional"))
    )
    (net (code "18") (name "/INPUT1_18") (class "Default")
      (node (ref "FI1") (pin "18") (pinfunction "1_18") (pintype "passive"))
      (node (ref "MOS18") (pin "1") (pinfunction "GATE_1") (pintype "bidirectional"))
    )
    (net (code "19") (name "/INPUT1_19") (class "Default")
      (node (ref "FI1") (pin "19") (pinfunction "1_19") (pintype "passive"))
      (node (ref "MOS19") (pin "1") (pinfunction "GATE_1") (pintype "bidirectional"))
    )
    (net (code "20") (name "/INPUT1_20") (class "Default")
      (node (ref "FI1") (pin "20") (pinfunction "1_20") (pintype "passive"))
      (node (ref "MOS20") (pin "1") (pinfunction "GATE_1") (pintype "bidirectional"))
    )
    (net (code "21") (name "/INPUT2_1") (class "Default")
      (node (ref "FI2") (pin "1") (pinfunction "1_1") (pintype "passive"))
      (node (ref "MOS21") (pin "1") (pinfunction "GATE_1") (pintype "bidirectional"))
    )
    (net (code "22") (name "/INPUT2_2") (class "Default")
      (node (ref "FI2") (pin "2") (pinfunction "1_2") (pintype "passive"))
      (node (ref "MOS22") (pin "1") (pinfunction "GATE_1") (pintype "bidirectional"))
    )
    (net (code "23") (name "/INPUT2_3") (class "Default")
      (node (ref "FI2") (pin "3") (pinfunction "1_3") (pintype "passive"))
      (node (ref "MOS23") (pin "1") (pinfunction "GATE_1") (pintype "bidirectional"))
    )
    (net (code "24") (name "/INPUT2_4") (class "Default")
      (node (ref "FI2") (pin "4") (pinfunction "1_4") (pintype "passive"))
      (node (ref "MOS24") (pin "1") (pinfunction "GATE_1") (pintype "bidirectional"))
    )
    (net (code "25") (name "/INPUT2_5") (class "Default")
      (node (ref "FI2") (pin "5") (pinfunction "1_5") (pintype "passive"))
      (node (ref "MOS25") (pin "1") (pinfunction "GATE_1") (pintype "bidirectional"))
    )
    (net (code "26") (name "/INPUT2_6") (class "Default")
      (node (ref "FI2") (pin "6") (pinfunction "1_6") (pintype "passive"))
      (node (ref "MOS26") (pin "1") (pinfunction "GATE_1") (pintype "bidirectional"))
    )
    (net (code "27") (name "/INPUT2_7") (class "Default")
      (node (ref "FI2") (pin "7") (pinfunction "1_7") (pintype "passive"))
      (node (ref "MOS27") (pin "1") (pinfunction "GATE_1") (pintype "bidirectional"))
    )
    (net (code "28") (name "/INPUT2_8") (class "Default")
      (node (ref "FI2") (pin "8") (pinfunction "1_8") (pintype "passive"))
      (node (ref "MOS28") (pin "1") (pinfunction "GATE_1") (pintype "bidirectional"))
    )
    (net (code "29") (name "/INPUT2_9") (class "Default")
      (node (ref "FI2") (pin "9") (pinfunction "1_9") (pintype "passive"))
      (node (ref "MOS29") (pin "1") (pinfunction "GATE_1") (pintype "bidirectional"))
    )
    (net (code "30") (name "/INPUT2_10") (class "Default")
      (node (ref "FI2") (pin "10") (pinfunction "1_10") (pintype "passive"))
      (node (ref "MOS30") (pin "1") (pinfunction "GATE_1") (pintype "bidirectional"))
    )
    (net (code "31") (name "/INPUT2_11") (class "Default")
      (node (ref "FI2") (pin "11") (pinfunction "1_11") (pintype "passive"))
      (node (ref "MOS31") (pin "1") (pinfunction "GATE_1") (pintype "bidirectional"))
    )
    (net (code "32") (name "/INPUT2_12") (class "Default")
      (node (ref "FI2") (pin "12") (pinfunction "1_12") (pintype "passive"))
      (node (ref "MOS32") (pin "1") (pinfunction "GATE_1") (pintype "bidirectional"))
    )
    (net (code "33") (name "/INPUT2_13") (class "Default")
      (node (ref "FI2") (pin "13") (pinfunction "1_13") (pintype "passive"))
      (node (ref "MOS33") (pin "1") (pinfunction "GATE_1") (pintype "bidirectional"))
    )
    (net (code "34") (name "/INPUT2_14") (class "Default")
      (node (ref "FI2") (pin "14") (pinfunction "1_14") (pintype "passive"))
      (node (ref "MOS34") (pin "1") (pinfunction "GATE_1") (pintype "bidirectional"))
    )
    (net (code "35") (name "/INPUT2_15") (class "Default")
      (node (ref "FI2") (pin "15") (pinfunction "1_15") (pintype "passive"))
      (node (ref "MOS35") (pin "1") (pinfunction "GATE_1") (pintype "bidirectional"))
    )
    (net (code "36") (name "/INPUT2_16") (class "Default")
      (node (ref "FI2") (pin "16") (pinfunction "1_16") (pintype "passive"))
      (node (ref "MOS36") (pin "1") (pinfunction "GATE_1") (pintype "bidirectional"))
    )
    (net (code "37") (name "/INPUT2_17") (class "Default")
      (node (ref "FI2") (pin "17") (pinfunction "1_17") (pintype "passive"))
      (node (ref "MOS37") (pin "1") (pinfunction "GATE_1") (pintype "bidirectional"))
    )
    (net (code "38") (name "/INPUT2_18") (class "Default")
      (node (ref "FI2") (pin "18") (pinfunction "1_18") (pintype "passive"))
      (node (ref "MOS38") (pin "1") (pinfunction "GATE_1") (pintype "bidirectional"))
    )
    (net (code "39") (name "/INPUT2_19") (class "Default")
      (node (ref "FI2") (pin "19") (pinfunction "1_19") (pintype "passive"))
      (node (ref "MOS39") (pin "1") (pinfunction "GATE_1") (pintype "bidirectional"))
    )
    (net (code "40") (name "/INPUT2_20") (class "Default")
      (node (ref "FI2") (pin "20") (pinfunction "1_20") (pintype "passive"))
      (node (ref "MOS40") (pin "1") (pinfunction "GATE_1") (pintype "bidirectional"))
    )
    (net (code "41") (name "/INPUT3_1") (class "Default")
      (node (ref "FI3") (pin "1") (pinfunction "1_1") (pintype "passive"))
      (node (ref "MOS41") (pin "1") (pinfunction "GATE_1") (pintype "bidirectional"))
    )
    (net (code "42") (name "/INPUT3_2") (class "Default")
      (node (ref "FI3") (pin "2") (pinfunction "1_2") (pintype "passive"))
      (node (ref "MOS42") (pin "1") (pinfunction "GATE_1") (pintype "bidirectional"))
    )
    (net (code "43") (name "/INPUT3_3") (class "Default")
      (node (ref "FI3") (pin "3") (pinfunction "1_3") (pintype "passive"))
      (node (ref "MOS43") (pin "1") (pinfunction "GATE_1") (pintype "bidirectional"))
    )
    (net (code "44") (name "/INPUT3_4") (class "Default")
      (node (ref "FI3") (pin "4") (pinfunction "1_4") (pintype "passive"))
      (node (ref "MOS44") (pin "1") (pinfunction "GATE_1") (pintype "bidirectional"))
    )
    (net (code "45") (name "/INPUT3_5") (class "Default")
      (node (ref "FI3") (pin "5") (pinfunction "1_5") (pintype "passive"))
      (node (ref "MOS45") (pin "1") (pinfunction "GATE_1") (pintype "bidirectional"))
    )
    (net (code "46") (name "/INPUT3_6") (class "Default")
      (node (ref "FI3") (pin "6") (pinfunction "1_6") (pintype "passive"))
      (node (ref "MOS46") (pin "1") (pinfunction "GATE_1") (pintype "bidirectional"))
    )
    (net (code "47") (name "/INPUT3_7") (class "Default")
      (node (ref "FI3") (pin "7") (pinfunction "1_7") (pintype "passive"))
      (node (ref "MOS47") (pin "1") (pinfunction "GATE_1") (pintype "bidirectional"))
    )
    (net (code "48") (name "/INPUT3_8") (class "Default")
      (node (ref "FI3") (pin "8") (pinfunction "1_8") (pintype "passive"))
      (node (ref "MOS48") (pin "1") (pinfunction "GATE_1") (pintype "bidirectional"))
    )
    (net (code "49") (name "/INPUT3_9") (class "Default")
      (node (ref "FI3") (pin "9") (pinfunction "1_9") (pintype "passive"))
      (node (ref "MOS49") (pin "1") (pinfunction "GATE_1") (pintype "bidirectional"))
    )
    (net (code "50") (name "/INPUT3_10") (class "Default")
      (node (ref "FI3") (pin "10") (pinfunction "1_10") (pintype "passive"))
      (node (ref "MOS50") (pin "1") (pinfunction "GATE_1") (pintype "bidirectional"))
    )
    (net (code "51") (name "/INPUT3_11") (class "Default")
      (node (ref "FI3") (pin "11") (pinfunction "1_11") (pintype "passive"))
      (node (ref "MOS51") (pin "1") (pinfunction "GATE_1") (pintype "bidirectional"))
    )
    (net (code "52") (name "/INPUT3_12") (class "Default")
      (node (ref "FI3") (pin "12") (pinfunction "1_12") (pintype "passive"))
      (node (ref "MOS52") (pin "1") (pinfunction "GATE_1") (pintype "bidirectional"))
    )
    (net (code "53") (name "/INPUT3_13") (class "Default")
      (node (ref "FI3") (pin "13") (pinfunction "1_13") (pintype "passive"))
      (node (ref "MOS53") (pin "1") (pinfunction "GATE_1") (pintype "bidirectional"))
    )
    (net (code "54") (name "/INPUT3_14") (class "Default")
      (node (ref "FI3") (pin "14") (pinfunction "1_14") (pintype "passive"))
      (node (ref "MOS54") (pin "1") (pinfunction "GATE_1") (pintype "bidirectional"))
    )
    (net (code "55") (name "/INPUT3_15") (class "Default")
      (node (ref "FI3") (pin "15") (pinfunction "1_15") (pintype "passive"))
      (node (ref "MOS55") (pin "1") (pinfunction "GATE_1") (pintype "bidirectional"))
    )
    (net (code "56") (name "/INPUT3_16") (class "Default")
      (node (ref "FI3") (pin "16") (pinfunction "1_16") (pintype "passive"))
      (node (ref "MOS56") (pin "1") (pinfunction "GATE_1") (pintype "bidirectional"))
    )
    (net (code "57") (name "/INPUT3_17") (class "Default")
      (node (ref "FI3") (pin "17") (pinfunction "1_17") (pintype "passive"))
      (node (ref "MOS57") (pin "1") (pinfunction "GATE_1") (pintype "bidirectional"))
    )
    (net (code "58") (name "/INPUT3_18") (class "Default")
      (node (ref "FI3") (pin "18") (pinfunction "1_18") (pintype "passive"))
      (node (ref "MOS58") (pin "1") (pinfunction "GATE_1") (pintype "bidirectional"))
    )
    (net (code "59") (name "/INPUT3_19") (class "Default")
      (node (ref "FI3") (pin "19") (pinfunction "1_19") (pintype "passive"))
      (node (ref "MOS59") (pin "1") (pinfunction "GATE_1") (pintype "bidirectional"))
    )
    (net (code "60") (name "/INPUT3_20") (class "Default")
      (node (ref "FI3") (pin "20") (pinfunction "1_20") (pintype "passive"))
      (node (ref "MOS60") (pin "1") (pinfunction "GATE_1") (pintype "bidirectional"))
    )
    (net (code "61") (name "/INPUT4_1") (class "Default")
      (node (ref "FI4") (pin "1") (pinfunction "1_1") (pintype "passive"))
      (node (ref "MOS61") (pin "1") (pinfunction "GATE_1") (pintype "bidirectional"))
    )
    (net (code "62") (name "/INPUT4_2") (class "Default")
      (node (ref "FI4") (pin "2") (pinfunction "1_2") (pintype "passive"))
      (node (ref "MOS62") (pin "1") (pinfunction "GATE_1") (pintype "bidirectional"))
    )
    (net (code "63") (name "/INPUT4_3") (class "Default")
      (node (ref "FI4") (pin "3") (pinfunction "1_3") (pintype "passive"))
      (node (ref "MOS63") (pin "1") (pinfunction "GATE_1") (pintype "bidirectional"))
    )
    (net (code "64") (name "/INPUT4_4") (class "Default")
      (node (ref "FI4") (pin "4") (pinfunction "1_4") (pintype "passive"))
      (node (ref "MOS64") (pin "1") (pinfunction "GATE_1") (pintype "bidirectional"))
    )
    (net (code "65") (name "/INPUT4_5") (class "Default")
      (node (ref "FI4") (pin "5") (pinfunction "1_5") (pintype "passive"))
      (node (ref "MOS65") (pin "1") (pinfunction "GATE_1") (pintype "bidirectional"))
    )
    (net (code "66") (name "/INPUT4_6") (class "Default")
      (node (ref "FI4") (pin "6") (pinfunction "1_6") (pintype "passive"))
      (node (ref "MOS66") (pin "1") (pinfunction "GATE_1") (pintype "bidirectional"))
    )
    (net (code "67") (name "/INPUT4_7") (class "Default")
      (node (ref "FI4") (pin "7") (pinfunction "1_7") (pintype "passive"))
      (node (ref "MOS67") (pin "1") (pinfunction "GATE_1") (pintype "bidirectional"))
    )
    (net (code "68") (name "/INPUT4_8") (class "Default")
      (node (ref "FI4") (pin "8") (pinfunction "1_8") (pintype "passive"))
      (node (ref "MOS68") (pin "1") (pinfunction "GATE_1") (pintype "bidirectional"))
    )
    (net (code "69") (name "/INPUT4_9") (class "Default")
      (node (ref "FI4") (pin "9") (pinfunction "1_9") (pintype "passive"))
      (node (ref "MOS69") (pin "1") (pinfunction "GATE_1") (pintype "bidirectional"))
    )
    (net (code "70") (name "/INPUT4_10") (class "Default")
      (node (ref "FI4") (pin "10") (pinfunction "1_10") (pintype "passive"))
      (node (ref "MOS70") (pin "1") (pinfunction "GATE_1") (pintype "bidirectional"))
    )
    (net (code "71") (name "/INPUT4_11") (class "Default")
      (node (ref "FI4") (pin "11") (pinfunction "1_11") (pintype "passive"))
      (node (ref "MOS71") (pin "1") (pinfunction "GATE_1") (pintype "bidirectional"))
    )
    (net (code "72") (name "/INPUT4_12") (class "Default")
      (node (ref "FI4") (pin "12") (pinfunction "1_12") (pintype "passive"))
      (node (ref "MOS72") (pin "1") (pinfunction "GATE_1") (pintype "bidirectional"))
    )
    (net (code "73") (name "/INPUT4_13") (class "Default")
      (node (ref "FI4") (pin "13") (pinfunction "1_13") (pintype "passive"))
      (node (ref "MOS73") (pin "1") (pinfunction "GATE_1") (pintype "bidirectional"))
    )
    (net (code "74") (name "/INPUT4_14") (class "Default")
      (node (ref "FI4") (pin "14") (pinfunction "1_14") (pintype "passive"))
      (node (ref "MOS74") (pin "1") (pinfunction "GATE_1") (pintype "bidirectional"))
    )
    (net (code "75") (name "/INPUT4_15") (class "Default")
      (node (ref "FI4") (pin "15") (pinfunction "1_15") (pintype "passive"))
      (node (ref "MOS75") (pin "1") (pinfunction "GATE_1") (pintype "bidirectional"))
    )
    (net (code "76") (name "/INPUT4_16") (class "Default")
      (node (ref "FI4") (pin "16") (pinfunction "1_16") (pintype "passive"))
      (node (ref "MOS76") (pin "1") (pinfunction "GATE_1") (pintype "bidirectional"))
    )
    (net (code "77") (name "/INPUT4_17") (class "Default")
      (node (ref "FI4") (pin "17") (pinfunction "1_17") (pintype "passive"))
      (node (ref "MOS77") (pin "1") (pinfunction "GATE_1") (pintype "bidirectional"))
    )
    (net (code "78") (name "/INPUT4_18") (class "Default")
      (node (ref "FI4") (pin "18") (pinfunction "1_18") (pintype "passive"))
      (node (ref "MOS78") (pin "1") (pinfunction "GATE_1") (pintype "bidirectional"))
    )
    (net (code "79") (name "/INPUT4_19") (class "Default")
      (node (ref "FI4") (pin "19") (pinfunction "1_19") (pintype "passive"))
      (node (ref "MOS79") (pin "1") (pinfunction "GATE_1") (pintype "bidirectional"))
    )
    (net (code "80") (name "/INPUT4_20") (class "Default")
      (node (ref "FI4") (pin "20") (pinfunction "1_20") (pintype "passive"))
      (node (ref "MOS80") (pin "1") (pinfunction "GATE_1") (pintype "bidirectional"))
    )
    (net (code "81") (name "/OUTPUT1_1") (class "Default")
      (node (ref "FO1") (pin "1") (pinfunction "1_1") (pintype "passive"))
      (node (ref "MOS1") (pin "2") (pinfunction "SOURCE_2") (pintype "bidirectional"))
    )
    (net (code "82") (name "/OUTPUT1_2") (class "Default")
      (node (ref "FO1") (pin "2") (pinfunction "1_2") (pintype "passive"))
      (node (ref "MOS2") (pin "2") (pinfunction "SOURCE_2") (pintype "bidirectional"))
    )
    (net (code "83") (name "/OUTPUT1_3") (class "Default")
      (node (ref "FO1") (pin "3") (pinfunction "1_3") (pintype "passive"))
      (node (ref "MOS3") (pin "2") (pinfunction "SOURCE_2") (pintype "bidirectional"))
    )
    (net (code "84") (name "/OUTPUT1_4") (class "Default")
      (node (ref "FO1") (pin "4") (pinfunction "1_4") (pintype "passive"))
      (node (ref "MOS4") (pin "2") (pinfunction "SOURCE_2") (pintype "bidirectional"))
    )
    (net (code "85") (name "/OUTPUT1_5") (class "Default")
      (node (ref "FO1") (pin "5") (pinfunction "1_5") (pintype "passive"))
      (node (ref "MOS5") (pin "2") (pinfunction "SOURCE_2") (pintype "bidirectional"))
    )
    (net (code "86") (name "/OUTPUT1_6") (class "Default")
      (node (ref "FO1") (pin "6") (pinfunction "1_6") (pintype "passive"))
      (node (ref "MOS6") (pin "2") (pinfunction "SOURCE_2") (pintype "bidirectional"))
    )
    (net (code "87") (name "/OUTPUT1_7") (class "Default")
      (node (ref "FO1") (pin "7") (pinfunction "1_7") (pintype "passive"))
      (node (ref "MOS7") (pin "2") (pinfunction "SOURCE_2") (pintype "bidirectional"))
    )
    (net (code "88") (name "/OUTPUT1_8") (class "Default")
      (node (ref "FO1") (pin "8") (pinfunction "1_8") (pintype "passive"))
      (node (ref "MOS8") (pin "2") (pinfunction "SOURCE_2") (pintype "bidirectional"))
    )
    (net (code "89") (name "/OUTPUT1_9") (class "Default")
      (node (ref "FO1") (pin "9") (pinfunction "1_9") (pintype "passive"))
      (node (ref "MOS9") (pin "2") (pinfunction "SOURCE_2") (pintype "bidirectional"))
    )
    (net (code "90") (name "/OUTPUT1_10") (class "Default")
      (node (ref "FO1") (pin "10") (pinfunction "1_10") (pintype "passive"))
      (node (ref "MOS10") (pin "2") (pinfunction "SOURCE_2") (pintype "bidirectional"))
    )
    (net (code "91") (name "/OUTPUT1_11") (class "Default")
      (node (ref "FO1") (pin "11") (pinfunction "1_11") (pintype "passive"))
      (node (ref "MOS11") (pin "2") (pinfunction "SOURCE_2") (pintype "bidirectional"))
    )
    (net (code "92") (name "/OUTPUT1_12") (class "Default")
      (node (ref "FO1") (pin "12") (pinfunction "1_12") (pintype "passive"))
      (node (ref "MOS12") (pin "2") (pinfunction "SOURCE_2") (pintype "bidirectional"))
    )
    (net (code "93") (name "/OUTPUT1_13") (class "Default")
      (node (ref "FO1") (pin "13") (pinfunction "1_13") (pintype "passive"))
      (node (ref "MOS13") (pin "2") (pinfunction "SOURCE_2") (pintype "bidirectional"))
    )
    (net (code "94") (name "/OUTPUT1_14") (class "Default")
      (node (ref "FO1") (pin "14") (pinfunction "1_14") (pintype "passive"))
      (node (ref "MOS14") (pin "2") (pinfunction "SOURCE_2") (pintype "bidirectional"))
    )
    (net (code "95") (name "/OUTPUT1_15") (class "Default")
      (node (ref "FO1") (pin "15") (pinfunction "1_15") (pintype "passive"))
      (node (ref "MOS15") (pin "2") (pinfunction "SOURCE_2") (pintype "bidirectional"))
    )
    (net (code "96") (name "/OUTPUT1_16") (class "Default")
      (node (ref "FO1") (pin "16") (pinfunction "1_16") (pintype "passive"))
      (node (ref "MOS16") (pin "2") (pinfunction "SOURCE_2") (pintype "bidirectional"))
    )
    (net (code "97") (name "/OUTPUT1_17") (class "Default")
      (node (ref "FO1") (pin "17") (pinfunction "1_17") (pintype "passive"))
      (node (ref "MOS17") (pin "2") (pinfunction "SOURCE_2") (pintype "bidirectional"))
    )
    (net (code "98") (name "/OUTPUT1_18") (class "Default")
      (node (ref "FO1") (pin "18") (pinfunction "1_18") (pintype "passive"))
      (node (ref "MOS18") (pin "2") (pinfunction "SOURCE_2") (pintype "bidirectional"))
    )
    (net (code "99") (name "/OUTPUT1_19") (class "Default")
      (node (ref "FO1") (pin "19") (pinfunction "1_19") (pintype "passive"))
      (node (ref "MOS19") (pin "2") (pinfunction "SOURCE_2") (pintype "bidirectional"))
    )
    (net (code "100") (name "/OUTPUT1_20") (class "Default")
      (node (ref "FO1") (pin "20") (pinfunction "1_20") (pintype "passive"))
      (node (ref "MOS20") (pin "2") (pinfunction "SOURCE_2") (pintype "bidirectional"))
    )
    (net (code "101") (name "/OUTPUT2_1") (class "Default")
      (node (ref "FO2") (pin "1") (pinfunction "1_1") (pintype "passive"))
      (node (ref "MOS21") (pin "2") (pinfunction "SOURCE_2") (pintype "bidirectional"))
    )
    (net (code "102") (name "/OUTPUT2_2") (class "Default")
      (node (ref "FO2") (pin "2") (pinfunction "1_2") (pintype "passive"))
      (node (ref "MOS22") (pin "2") (pinfunction "SOURCE_2") (pintype "bidirectional"))
    )
    (net (code "103") (name "/OUTPUT2_3") (class "Default")
      (node (ref "FO2") (pin "3") (pinfunction "1_3") (pintype "passive"))
      (node (ref "MOS23") (pin "2") (pinfunction "SOURCE_2") (pintype "bidirectional"))
    )
    (net (code "104") (name "/OUTPUT2_4") (class "Default")
      (node (ref "FO2") (pin "4") (pinfunction "1_4") (pintype "passive"))
      (node (ref "MOS24") (pin "2") (pinfunction "SOURCE_2") (pintype "bidirectional"))
    )
    (net (code "105") (name "/OUTPUT2_5") (class "Default")
      (node (ref "FO2") (pin "5") (pinfunction "1_5") (pintype "passive"))
      (node (ref "MOS25") (pin "2") (pinfunction "SOURCE_2") (pintype "bidirectional"))
    )
    (net (code "106") (name "/OUTPUT2_6") (class "Default")
      (node (ref "FO2") (pin "6") (pinfunction "1_6") (pintype "passive"))
      (node (ref "MOS26") (pin "2") (pinfunction "SOURCE_2") (pintype "bidirectional"))
    )
    (net (code "107") (name "/OUTPUT2_7") (class "Default")
      (node (ref "FO2") (pin "7") (pinfunction "1_7") (pintype "passive"))
      (node (ref "MOS27") (pin "2") (pinfunction "SOURCE_2") (pintype "bidirectional"))
    )
    (net (code "108") (name "/OUTPUT2_8") (class "Default")
      (node (ref "FO2") (pin "8") (pinfunction "1_8") (pintype "passive"))
      (node (ref "MOS28") (pin "2") (pinfunction "SOURCE_2") (pintype "bidirectional"))
    )
    (net (code "109") (name "/OUTPUT2_9") (class "Default")
      (node (ref "FO2") (pin "9") (pinfunction "1_9") (pintype "passive"))
      (node (ref "MOS29") (pin "2") (pinfunction "SOURCE_2") (pintype "bidirectional"))
    )
    (net (code "110") (name "/OUTPUT2_10") (class "Default")
      (node (ref "FO2") (pin "10") (pinfunction "1_10") (pintype "passive"))
      (node (ref "MOS30") (pin "2") (pinfunction "SOURCE_2") (pintype "bidirectional"))
    )
    (net (code "111") (name "/OUTPUT2_11") (class "Default")
      (node (ref "FO2") (pin "11") (pinfunction "1_11") (pintype "passive"))
      (node (ref "MOS31") (pin "2") (pinfunction "SOURCE_2") (pintype "bidirectional"))
    )
    (net (code "112") (name "/OUTPUT2_12") (class "Default")
      (node (ref "FO2") (pin "12") (pinfunction "1_12") (pintype "passive"))
      (node (ref "MOS32") (pin "2") (pinfunction "SOURCE_2") (pintype "bidirectional"))
    )
    (net (code "113") (name "/OUTPUT2_13") (class "Default")
      (node (ref "FO2") (pin "13") (pinfunction "1_13") (pintype "passive"))
      (node (ref "MOS33") (pin "2") (pinfunction "SOURCE_2") (pintype "bidirectional"))
    )
    (net (code "114") (name "/OUTPUT2_14") (class "Default")
      (node (ref "FO2") (pin "14") (pinfunction "1_14") (pintype "passive"))
      (node (ref "MOS34") (pin "2") (pinfunction "SOURCE_2") (pintype "bidirectional"))
    )
    (net (code "115") (name "/OUTPUT2_15") (class "Default")
      (node (ref "FO2") (pin "15") (pinfunction "1_15") (pintype "passive"))
      (node (ref "MOS35") (pin "2") (pinfunction "SOURCE_2") (pintype "bidirectional"))
    )
    (net (code "116") (name "/OUTPUT2_16") (class "Default")
      (node (ref "FO2") (pin "16") (pinfunction "1_16") (pintype "passive"))
      (node (ref "MOS36") (pin "2") (pinfunction "SOURCE_2") (pintype "bidirectional"))
    )
    (net (code "117") (name "/OUTPUT2_17") (class "Default")
      (node (ref "FO2") (pin "17") (pinfunction "1_17") (pintype "passive"))
      (node (ref "MOS37") (pin "2") (pinfunction "SOURCE_2") (pintype "bidirectional"))
    )
    (net (code "118") (name "/OUTPUT2_18") (class "Default")
      (node (ref "FO2") (pin "18") (pinfunction "1_18") (pintype "passive"))
      (node (ref "MOS38") (pin "2") (pinfunction "SOURCE_2") (pintype "bidirectional"))
    )
    (net (code "119") (name "/OUTPUT2_19") (class "Default")
      (node (ref "FO2") (pin "19") (pinfunction "1_19") (pintype "passive"))
      (node (ref "MOS39") (pin "2") (pinfunction "SOURCE_2") (pintype "bidirectional"))
    )
    (net (code "120") (name "/OUTPUT2_20") (class "Default")
      (node (ref "FO2") (pin "20") (pinfunction "1_20") (pintype "passive"))
      (node (ref "MOS40") (pin "2") (pinfunction "SOURCE_2") (pintype "bidirectional"))
    )
    (net (code "121") (name "/OUTPUT3_1") (class "Default")
      (node (ref "FO3") (pin "1") (pinfunction "1_1") (pintype "passive"))
      (node (ref "MOS41") (pin "2") (pinfunction "SOURCE_2") (pintype "bidirectional"))
    )
    (net (code "122") (name "/OUTPUT3_2") (class "Default")
      (node (ref "FO3") (pin "2") (pinfunction "1_2") (pintype "passive"))
      (node (ref "MOS42") (pin "2") (pinfunction "SOURCE_2") (pintype "bidirectional"))
    )
    (net (code "123") (name "/OUTPUT3_3") (class "Default")
      (node (ref "FO3") (pin "3") (pinfunction "1_3") (pintype "passive"))
      (node (ref "MOS43") (pin "2") (pinfunction "SOURCE_2") (pintype "bidirectional"))
    )
    (net (code "124") (name "/OUTPUT3_4") (class "Default")
      (node (ref "FO3") (pin "4") (pinfunction "1_4") (pintype "passive"))
      (node (ref "MOS44") (pin "2") (pinfunction "SOURCE_2") (pintype "bidirectional"))
    )
    (net (code "125") (name "/OUTPUT3_5") (class "Default")
      (node (ref "FO3") (pin "5") (pinfunction "1_5") (pintype "passive"))
      (node (ref "MOS45") (pin "2") (pinfunction "SOURCE_2") (pintype "bidirectional"))
    )
    (net (code "126") (name "/OUTPUT3_6") (class "Default")
      (node (ref "FO3") (pin "6") (pinfunction "1_6") (pintype "passive"))
      (node (ref "MOS46") (pin "2") (pinfunction "SOURCE_2") (pintype "bidirectional"))
    )
    (net (code "127") (name "/OUTPUT3_7") (class "Default")
      (node (ref "FO3") (pin "7") (pinfunction "1_7") (pintype "passive"))
      (node (ref "MOS47") (pin "2") (pinfunction "SOURCE_2") (pintype "bidirectional"))
    )
    (net (code "128") (name "/OUTPUT3_8") (class "Default")
      (node (ref "FO3") (pin "8") (pinfunction "1_8") (pintype "passive"))
      (node (ref "MOS48") (pin "2") (pinfunction "SOURCE_2") (pintype "bidirectional"))
    )
    (net (code "129") (name "/OUTPUT3_9") (class "Default")
      (node (ref "FO3") (pin "9") (pinfunction "1_9") (pintype "passive"))
      (node (ref "MOS49") (pin "2") (pinfunction "SOURCE_2") (pintype "bidirectional"))
    )
    (net (code "130") (name "/OUTPUT3_10") (class "Default")
      (node (ref "FO3") (pin "10") (pinfunction "1_10") (pintype "passive"))
      (node (ref "MOS50") (pin "2") (pinfunction "SOURCE_2") (pintype "bidirectional"))
    )
    (net (code "131") (name "/OUTPUT3_11") (class "Default")
      (node (ref "FO3") (pin "11") (pinfunction "1_11") (pintype "passive"))
      (node (ref "MOS51") (pin "2") (pinfunction "SOURCE_2") (pintype "bidirectional"))
    )
    (net (code "132") (name "/OUTPUT3_12") (class "Default")
      (node (ref "FO3") (pin "12") (pinfunction "1_12") (pintype "passive"))
      (node (ref "MOS52") (pin "2") (pinfunction "SOURCE_2") (pintype "bidirectional"))
    )
    (net (code "133") (name "/OUTPUT3_13") (class "Default")
      (node (ref "FO3") (pin "13") (pinfunction "1_13") (pintype "passive"))
      (node (ref "MOS53") (pin "2") (pinfunction "SOURCE_2") (pintype "bidirectional"))
    )
    (net (code "134") (name "/OUTPUT3_14") (class "Default")
      (node (ref "FO3") (pin "14") (pinfunction "1_14") (pintype "passive"))
      (node (ref "MOS54") (pin "2") (pinfunction "SOURCE_2") (pintype "bidirectional"))
    )
    (net (code "135") (name "/OUTPUT3_15") (class "Default")
      (node (ref "FO3") (pin "15") (pinfunction "1_15") (pintype "passive"))
      (node (ref "MOS55") (pin "2") (pinfunction "SOURCE_2") (pintype "bidirectional"))
    )
    (net (code "136") (name "/OUTPUT3_16") (class "Default")
      (node (ref "FO3") (pin "16") (pinfunction "1_16") (pintype "passive"))
      (node (ref "MOS56") (pin "2") (pinfunction "SOURCE_2") (pintype "bidirectional"))
    )
    (net (code "137") (name "/OUTPUT3_17") (class "Default")
      (node (ref "FO3") (pin "17") (pinfunction "1_17") (pintype "passive"))
      (node (ref "MOS57") (pin "2") (pinfunction "SOURCE_2") (pintype "bidirectional"))
    )
    (net (code "138") (name "/OUTPUT3_18") (class "Default")
      (node (ref "FO3") (pin "18") (pinfunction "1_18") (pintype "passive"))
      (node (ref "MOS58") (pin "2") (pinfunction "SOURCE_2") (pintype "bidirectional"))
    )
    (net (code "139") (name "/OUTPUT3_19") (class "Default")
      (node (ref "FO3") (pin "19") (pinfunction "1_19") (pintype "passive"))
      (node (ref "MOS59") (pin "2") (pinfunction "SOURCE_2") (pintype "bidirectional"))
    )
    (net (code "140") (name "/OUTPUT3_20") (class "Default")
      (node (ref "FO3") (pin "20") (pinfunction "1_20") (pintype "passive"))
      (node (ref "MOS60") (pin "2") (pinfunction "SOURCE_2") (pintype "bidirectional"))
    )
    (net (code "141") (name "/OUTPUT4_1") (class "Default")
      (node (ref "FO4") (pin "1") (pinfunction "1_1") (pintype "passive"))
      (node (ref "MOS61") (pin "2") (pinfunction "SOURCE_2") (pintype "bidirectional"))
    )
    (net (code "142") (name "/OUTPUT4_2") (class "Default")
      (node (ref "FO4") (pin "2") (pinfunction "1_2") (pintype "passive"))
      (node (ref "MOS62") (pin "2") (pinfunction "SOURCE_2") (pintype "bidirectional"))
    )
    (net (code "143") (name "/OUTPUT4_3") (class "Default")
      (node (ref "FO4") (pin "3") (pinfunction "1_3") (pintype "passive"))
      (node (ref "MOS63") (pin "2") (pinfunction "SOURCE_2") (pintype "bidirectional"))
    )
    (net (code "144") (name "/OUTPUT4_4") (class "Default")
      (node (ref "FO4") (pin "4") (pinfunction "1_4") (pintype "passive"))
      (node (ref "MOS64") (pin "2") (pinfunction "SOURCE_2") (pintype "bidirectional"))
    )
    (net (code "145") (name "/OUTPUT4_5") (class "Default")
      (node (ref "FO4") (pin "5") (pinfunction "1_5") (pintype "passive"))
      (node (ref "MOS65") (pin "2") (pinfunction "SOURCE_2") (pintype "bidirectional"))
    )
    (net (code "146") (name "/OUTPUT4_6") (class "Default")
      (node (ref "FO4") (pin "6") (pinfunction "1_6") (pintype "passive"))
      (node (ref "MOS66") (pin "2") (pinfunction "SOURCE_2") (pintype "bidirectional"))
    )
    (net (code "147") (name "/OUTPUT4_7") (class "Default")
      (node (ref "FO4") (pin "7") (pinfunction "1_7") (pintype "passive"))
      (node (ref "MOS67") (pin "2") (pinfunction "SOURCE_2") (pintype "bidirectional"))
    )
    (net (code "148") (name "/OUTPUT4_8") (class "Default")
      (node (ref "FO4") (pin "8") (pinfunction "1_8") (pintype "passive"))
      (node (ref "MOS68") (pin "2") (pinfunction "SOURCE_2") (pintype "bidirectional"))
    )
    (net (code "149") (name "/OUTPUT4_9") (class "Default")
      (node (ref "FO4") (pin "9") (pinfunction "1_9") (pintype "passive"))
      (node (ref "MOS69") (pin "2") (pinfunction "SOURCE_2") (pintype "bidirectional"))
    )
    (net (code "150") (name "/OUTPUT4_10") (class "Default")
      (node (ref "FO4") (pin "10") (pinfunction "1_10") (pintype "passive"))
      (node (ref "MOS70") (pin "2") (pinfunction "SOURCE_2") (pintype "bidirectional"))
    )
    (net (code "151") (name "/OUTPUT4_11") (class "Default")
      (node (ref "FO4") (pin "11") (pinfunction "1_11") (pintype "passive"))
      (node (ref "MOS71") (pin "2") (pinfunction "SOURCE_2") (pintype "bidirectional"))
    )
    (net (code "152") (name "/OUTPUT4_12") (class "Default")
      (node (ref "FO4") (pin "12") (pinfunction "1_12") (pintype "passive"))
      (node (ref "MOS72") (pin "2") (pinfunction "SOURCE_2") (pintype "bidirectional"))
    )
    (net (code "153") (name "/OUTPUT4_13") (class "Default")
      (node (ref "FO4") (pin "13") (pinfunction "1_13") (pintype "passive"))
      (node (ref "MOS73") (pin "2") (pinfunction "SOURCE_2") (pintype "bidirectional"))
    )
    (net (code "154") (name "/OUTPUT4_14") (class "Default")
      (node (ref "FO4") (pin "14") (pinfunction "1_14") (pintype "passive"))
      (node (ref "MOS74") (pin "2") (pinfunction "SOURCE_2") (pintype "bidirectional"))
    )
    (net (code "155") (name "/OUTPUT4_15") (class "Default")
      (node (ref "FO4") (pin "15") (pinfunction "1_15") (pintype "passive"))
      (node (ref "MOS75") (pin "2") (pinfunction "SOURCE_2") (pintype "bidirectional"))
    )
    (net (code "156") (name "/OUTPUT4_16") (class "Default")
      (node (ref "FO4") (pin "16") (pinfunction "1_16") (pintype "passive"))
      (node (ref "MOS76") (pin "2") (pinfunction "SOURCE_2") (pintype "bidirectional"))
    )
    (net (code "157") (name "/OUTPUT4_17") (class "Default")
      (node (ref "FO4") (pin "17") (pinfunction "1_17") (pintype "passive"))
      (node (ref "MOS77") (pin "2") (pinfunction "SOURCE_2") (pintype "bidirectional"))
    )
    (net (code "158") (name "/OUTPUT4_18") (class "Default")
      (node (ref "FO4") (pin "18") (pinfunction "1_18") (pintype "passive"))
      (node (ref "MOS78") (pin "2") (pinfunction "SOURCE_2") (pintype "bidirectional"))
    )
    (net (code "159") (name "/OUTPUT4_19") (class "Default")
      (node (ref "FO4") (pin "19") (pinfunction "1_19") (pintype "passive"))
      (node (ref "MOS79") (pin "2") (pinfunction "SOURCE_2") (pintype "bidirectional"))
    )
    (net (code "160") (name "/OUTPUT4_20") (class "Default")
      (node (ref "FO4") (pin "20") (pinfunction "1_20") (pintype "passive"))
      (node (ref "MOS80") (pin "2") (pinfunction "SOURCE_2") (pintype "bidirectional"))
    )
    (net (code "161") (name "/VIN") (class "Default")
      (node (ref "JP1") (pin "1") (pinfunction "1_1") (pintype "passive"))
      (node (ref "JP2") (pin "1") (pinfunction "1_1") (pintype "passive"))
      (node (ref "LDO") (pin "IN") (pinfunction "IN_IN") (pintype "bidirectional"))
      (node (ref "LDO_C1") (pin "1") (pinfunction "1_1") (pintype "passive"))
      (node (ref "LDO_R3") (pin "1") (pinfunction "1_1") (pintype "passive"))
    )
    (net (code "162") (name "/VOUT") (class "Default")
      (node (ref "LDO") (pin "OUT") (pinfunction "OUT_OUT") (pintype "bidirectional"))
      (node (ref "LDO_C2") (pin "1") (pinfunction "1_1") (pintype "passive"))
      (node (ref "LDO_R1") (pin "2") (pinfunction "2_2") (pintype "passive"))
      (node (ref "R1") (pin "1") (pinfunction "1_1") (pintype "passive"))
      (node (ref "R10") (pin "1") (pinfunction "1_1") (pintype "passive"))
      (node (ref "R11") (pin "1") (pinfunction "1_1") (pintype "passive"))
      (node (ref "R12") (pin "1") (pinfunction "1_1") (pintype "passive"))
      (node (ref "R13") (pin "1") (pinfunction "1_1") (pintype "passive"))
      (node (ref "R14") (pin "1") (pinfunction "1_1") (pintype "passive"))
      (node (ref "R15") (pin "1") (pinfunction "1_1") (pintype "passive"))
      (node (ref "R16") (pin "1") (pinfunction "1_1") (pintype "passive"))
      (node (ref "R17") (pin "1") (pinfunction "1_1") (pintype "passive"))
      (node (ref "R18") (pin "1") (pinfunction "1_1") (pintype "passive"))
      (node (ref "R19") (pin "1") (pinfunction "1_1") (pintype "passive"))
      (node (ref "R2") (pin "1") (pinfunction "1_1") (pintype "passive"))
      (node (ref "R20") (pin "1") (pinfunction "1_1") (pintype "passive"))
      (node (ref "R21") (pin "1") (pinfunction "1_1") (pintype "passive"))
      (node (ref "R22") (pin "1") (pinfunction "1_1") (pintype "passive"))
      (node (ref "R23") (pin "1") (pinfunction "1_1") (pintype "passive"))
      (node (ref "R24") (pin "1") (pinfunction "1_1") (pintype "passive"))
      (node (ref "R25") (pin "1") (pinfunction "1_1") (pintype "passive"))
      (node (ref "R26") (pin "1") (pinfunction "1_1") (pintype "passive"))
      (node (ref "R27") (pin "1") (pinfunction "1_1") (pintype "passive"))
      (node (ref "R28") (pin "1") (pinfunction "1_1") (pintype "passive"))
      (node (ref "R29") (pin "1") (pinfunction "1_1") (pintype "passive"))
      (node (ref "R3") (pin "1") (pinfunction "1_1") (pintype "passive"))
      (node (ref "R30") (pin "1") (pinfunction "1_1") (pintype "passive"))
      (node (ref "R31") (pin "1") (pinfunction "1_1") (pintype "passive"))
      (node (ref "R32") (pin "1") (pinfunction "1_1") (pintype "passive"))
      (node (ref "R33") (pin "1") (pinfunction "1_1") (pintype "passive"))
      (node (ref "R34") (pin "1") (pinfunction "1_1") (pintype "passive"))
      (node (ref "R35") (pin "1") (pinfunction "1_1") (pintype "passive"))
      (node (ref "R36") (pin "1") (pinfunction "1_1") (pintype "passive"))
      (node (ref "R37") (pin "1") (pinfunction "1_1") (pintype "passive"))
      (node (ref "R38") (pin "1") (pinfunction "1_1") (pintype "passive"))
      (node (ref "R39") (pin "1") (pinfunction "1_1") (pintype "passive"))
      (node (ref "R4") (pin "1") (pinfunction "1_1") (pintype "passive"))
      (node (ref "R40") (pin "1") (pinfunction "1_1") (pintype "passive"))
      (node (ref "R41") (pin "1") (pinfunction "1_1") (pintype "passive"))
      (node (ref "R42") (pin "1") (pinfunction "1_1") (pintype "passive"))
      (node (ref "R43") (pin "1") (pinfunction "1_1") (pintype "passive"))
      (node (ref "R44") (pin "1") (pinfunction "1_1") (pintype "passive"))
      (node (ref "R45") (pin "1") (pinfunction "1_1") (pintype "passive"))
      (node (ref "R46") (pin "1") (pinfunction "1_1") (pintype "passive"))
      (node (ref "R47") (pin "1") (pinfunction "1_1") (pintype "passive"))
      (node (ref "R48") (pin "1") (pinfunction "1_1") (pintype "passive"))
      (node (ref "R49") (pin "1") (pinfunction "1_1") (pintype "passive"))
      (node (ref "R5") (pin "1") (pinfunction "1_1") (pintype "passive"))
      (node (ref "R50") (pin "1") (pinfunction "1_1") (pintype "passive"))
      (node (ref "R51") (pin "1") (pinfunction "1_1") (pintype "passive"))
      (node (ref "R52") (pin "1") (pinfunction "1_1") (pintype "passive"))
      (node (ref "R53") (pin "1") (pinfunction "1_1") (pintype "passive"))
      (node (ref "R54") (pin "1") (pinfunction "1_1") (pintype "passive"))
      (node (ref "R55") (pin "1") (pinfunction "1_1") (pintype "passive"))
      (node (ref "R56") (pin "1") (pinfunction "1_1") (pintype "passive"))
      (node (ref "R57") (pin "1") (pinfunction "1_1") (pintype "passive"))
      (node (ref "R58") (pin "1") (pinfunction "1_1") (pintype "passive"))
      (node (ref "R59") (pin "1") (pinfunction "1_1") (pintype "passive"))
      (node (ref "R6") (pin "1") (pinfunction "1_1") (pintype "passive"))
      (node (ref "R60") (pin "1") (pinfunction "1_1") (pintype "passive"))
      (node (ref "R61") (pin "1") (pinfunction "1_1") (pintype "passive"))
      (node (ref "R62") (pin "1") (pinfunction "1_1") (pintype "passive"))
      (node (ref "R63") (pin "1") (pinfunction "1_1") (pintype "passive"))
      (node (ref "R64") (pin "1") (pinfunction "1_1") (pintype "passive"))
      (node (ref "R65") (pin "1") (pinfunction "1_1") (pintype "passive"))
      (node (ref "R66") (pin "1") (pinfunction "1_1") (pintype "passive"))
      (node (ref "R67") (pin "1") (pinfunction "1_1") (pintype "passive"))
      (node (ref "R68") (pin "1") (pinfunction "1_1") (pintype "passive"))
      (node (ref "R69") (pin "1") (pinfunction "1_1") (pintype "passive"))
      (node (ref "R7") (pin "1") (pinfunction "1_1") (pintype "passive"))
      (node (ref "R70") (pin "1") (pinfunction "1_1") (pintype "passive"))
      (node (ref "R71") (pin "1") (pinfunction "1_1") (pintype "passive"))
      (node (ref "R72") (pin "1") (pinfunction "1_1") (pintype "passive"))
      (node (ref "R73") (pin "1") (pinfunction "1_1") (pintype "passive"))
      (node (ref "R74") (pin "1") (pinfunction "1_1") (pintype "passive"))
      (node (ref "R75") (pin "1") (pinfunction "1_1") (pintype "passive"))
      (node (ref "R76") (pin "1") (pinfunction "1_1") (pintype "passive"))
      (node (ref "R77") (pin "1") (pinfunction "1_1") (pintype "passive"))
      (node (ref "R78") (pin "1") (pinfunction "1_1") (pintype "passive"))
      (node (ref "R79") (pin "1") (pinfunction "1_1") (pintype "passive"))
      (node (ref "R8") (pin "1") (pinfunction "1_1") (pintype "passive"))
      (node (ref "R80") (pin "1") (pinfunction "1_1") (pintype "passive"))
      (node (ref "R9") (pin "1") (pinfunction "1_1") (pintype "passive"))
    )
    (net (code "163") (name "GND") (class "Default")
      (node (ref "JP1") (pin "2") (pinfunction "2_2") (pintype "passive"))
      (node (ref "JP2") (pin "2") (pinfunction "2_2") (pintype "passive"))
      (node (ref "LDO") (pin "DAP") (pinfunction "DAP_DAP") (pintype "bidirectional"))
      (node (ref "LDO") (pin "GND") (pinfunction "GND_GND") (pintype "bidirectional"))
      (node (ref "LDO_C1") (pin "2") (pinfunction "2_2") (pintype "passive"))
      (node (ref "LDO_C2") (pin "2") (pinfunction "2_2") (pintype "passive"))
      (node (ref "LDO_R2") (pin "1") (pinfunction "1_1") (pintype "passive"))
    )
    (net (code "164") (name "Net-(LDO-PadADJ)") (class "Default")
      (node (ref "LDO") (pin "ADJ") (pinfunction "ADJ_ADJ") (pintype "bidirectional"))
      (node (ref "LDO_R1") (pin "1") (pinfunction "1_1") (pintype "passive"))
      (node (ref "LDO_R2") (pin "2") (pinfunction "2_2") (pintype "passive"))
    )
    (net (code "165") (name "Net-(LDO-PadEN)") (class "Default")
      (node (ref "LDO") (pin "EN") (pinfunction "EN_EN") (pintype "bidirectional"))
      (node (ref "LDO_R3") (pin "2") (pinfunction "2_2") (pintype "passive"))
    )
    (net (code "166") (name "Net-(MOS1-DRAIN)") (class "Default")
      (node (ref "MOS1") (pin "3") (pinfunction "DRAIN_3") (pintype "bidirectional"))
      (node (ref "R1") (pin "2") (pinfunction "2_2") (pintype "passive"))
    )
    (net (code "167") (name "Net-(MOS2-DRAIN)") (class "Default")
      (node (ref "MOS2") (pin "3") (pinfunction "DRAIN_3") (pintype "bidirectional"))
      (node (ref "R2") (pin "2") (pinfunction "2_2") (pintype "passive"))
    )
    (net (code "168") (name "Net-(MOS3-DRAIN)") (class "Default")
      (node (ref "MOS3") (pin "3") (pinfunction "DRAIN_3") (pintype "bidirectional"))
      (node (ref "R3") (pin "2") (pinfunction "2_2") (pintype "passive"))
    )
    (net (code "169") (name "Net-(MOS4-DRAIN)") (class "Default")
      (node (ref "MOS4") (pin "3") (pinfunction "DRAIN_3") (pintype "bidirectional"))
      (node (ref "R4") (pin "2") (pinfunction "2_2") (pintype "passive"))
    )
    (net (code "170") (name "Net-(MOS5-DRAIN)") (class "Default")
      (node (ref "MOS5") (pin "3") (pinfunction "DRAIN_3") (pintype "bidirectional"))
      (node (ref "R5") (pin "2") (pinfunction "2_2") (pintype "passive"))
    )
    (net (code "171") (name "Net-(MOS6-DRAIN)") (class "Default")
      (node (ref "MOS6") (pin "3") (pinfunction "DRAIN_3") (pintype "bidirectional"))
      (node (ref "R6") (pin "2") (pinfunction "2_2") (pintype "passive"))
    )
    (net (code "172") (name "Net-(MOS7-DRAIN)") (class "Default")
      (node (ref "MOS7") (pin "3") (pinfunction "DRAIN_3") (pintype "bidirectional"))
      (node (ref "R7") (pin "2") (pinfunction "2_2") (pintype "passive"))
    )
    (net (code "173") (name "Net-(MOS8-DRAIN)") (class "Default")
      (node (ref "MOS8") (pin "3") (pinfunction "DRAIN_3") (pintype "bidirectional"))
      (node (ref "R8") (pin "2") (pinfunction "2_2") (pintype "passive"))
    )
    (net (code "174") (name "Net-(MOS9-DRAIN)") (class "Default")
      (node (ref "MOS9") (pin "3") (pinfunction "DRAIN_3") (pintype "bidirectional"))
      (node (ref "R9") (pin "2") (pinfunction "2_2") (pintype "passive"))
    )
    (net (code "175") (name "Net-(MOS10-DRAIN)") (class "Default")
      (node (ref "MOS10") (pin "3") (pinfunction "DRAIN_3") (pintype "bidirectional"))
      (node (ref "R10") (pin "2") (pinfunction "2_2") (pintype "passive"))
    )
    (net (code "176") (name "Net-(MOS11-DRAIN)") (class "Default")
      (node (ref "MOS11") (pin "3") (pinfunction "DRAIN_3") (pintype "bidirectional"))
      (node (ref "R11") (pin "2") (pinfunction "2_2") (pintype "passive"))
    )
    (net (code "177") (name "Net-(MOS12-DRAIN)") (class "Default")
      (node (ref "MOS12") (pin "3") (pinfunction "DRAIN_3") (pintype "bidirectional"))
      (node (ref "R12") (pin "2") (pinfunction "2_2") (pintype "passive"))
    )
    (net (code "178") (name "Net-(MOS13-DRAIN)") (class "Default")
      (node (ref "MOS13") (pin "3") (pinfunction "DRAIN_3") (pintype "bidirectional"))
      (node (ref "R13") (pin "2") (pinfunction "2_2") (pintype "passive"))
    )
    (net (code "179") (name "Net-(MOS14-DRAIN)") (class "Default")
      (node (ref "MOS14") (pin "3") (pinfunction "DRAIN_3") (pintype "bidirectional"))
      (node (ref "R14") (pin "2") (pinfunction "2_2") (pintype "passive"))
    )
    (net (code "180") (name "Net-(MOS15-DRAIN)") (class "Default")
      (node (ref "MOS15") (pin "3") (pinfunction "DRAIN_3") (pintype "bidirectional"))
      (node (ref "R15") (pin "2") (pinfunction "2_2") (pintype "passive"))
    )
    (net (code "181") (name "Net-(MOS16-DRAIN)") (class "Default")
      (node (ref "MOS16") (pin "3") (pinfunction "DRAIN_3") (pintype "bidirectional"))
      (node (ref "R16") (pin "2") (pinfunction "2_2") (pintype "passive"))
    )
    (net (code "182") (name "Net-(MOS17-DRAIN)") (class "Default")
      (node (ref "MOS17") (pin "3") (pinfunction "DRAIN_3") (pintype "bidirectional"))
      (node (ref "R17") (pin "2") (pinfunction "2_2") (pintype "passive"))
    )
    (net (code "183") (name "Net-(MOS18-DRAIN)") (class "Default")
      (node (ref "MOS18") (pin "3") (pinfunction "DRAIN_3") (pintype "bidirectional"))
      (node (ref "R18") (pin "2") (pinfunction "2_2") (pintype "passive"))
    )
    (net (code "184") (name "Net-(MOS19-DRAIN)") (class "Default")
      (node (ref "MOS19") (pin "3") (pinfunction "DRAIN_3") (pintype "bidirectional"))
      (node (ref "R19") (pin "2") (pinfunction "2_2") (pintype "passive"))
    )
    (net (code "185") (name "Net-(MOS20-DRAIN)") (class "Default")
      (node (ref "MOS20") (pin "3") (pinfunction "DRAIN_3") (pintype "bidirectional"))
      (node (ref "R20") (pin "2") (pinfunction "2_2") (pintype "passive"))
    )
    (net (code "186") (name "Net-(MOS21-DRAIN)") (class "Default")
      (node (ref "MOS21") (pin "3") (pinfunction "DRAIN_3") (pintype "bidirectional"))
      (node (ref "R21") (pin "2") (pinfunction "2_2") (pintype "passive"))
    )
    (net (code "187") (name "Net-(MOS22-DRAIN)") (class "Default")
      (node (ref "MOS22") (pin "3") (pinfunction "DRAIN_3") (pintype "bidirectional"))
      (node (ref "R22") (pin "2") (pinfunction "2_2") (pintype "passive"))
    )
    (net (code "188") (name "Net-(MOS23-DRAIN)") (class "Default")
      (node (ref "MOS23") (pin "3") (pinfunction "DRAIN_3") (pintype "bidirectional"))
      (node (ref "R23") (pin "2") (pinfunction "2_2") (pintype "passive"))
    )
    (net (code "189") (name "Net-(MOS24-DRAIN)") (class "Default")
      (node (ref "MOS24") (pin "3") (pinfunction "DRAIN_3") (pintype "bidirectional"))
      (node (ref "R24") (pin "2") (pinfunction "2_2") (pintype "passive"))
    )
    (net (code "190") (name "Net-(MOS25-DRAIN)") (class "Default")
      (node (ref "MOS25") (pin "3") (pinfunction "DRAIN_3") (pintype "bidirectional"))
      (node (ref "R25") (pin "2") (pinfunction "2_2") (pintype "passive"))
    )
    (net (code "191") (name "Net-(MOS26-DRAIN)") (class "Default")
      (node (ref "MOS26") (pin "3") (pinfunction "DRAIN_3") (pintype "bidirectional"))
      (node (ref "R26") (pin "2") (pinfunction "2_2") (pintype "passive"))
    )
    (net (code "192") (name "Net-(MOS27-DRAIN)") (class "Default")
      (node (ref "MOS27") (pin "3") (pinfunction "DRAIN_3") (pintype "bidirectional"))
      (node (ref "R27") (pin "2") (pinfunction "2_2") (pintype "passive"))
    )
    (net (code "193") (name "Net-(MOS28-DRAIN)") (class "Default")
      (node (ref "MOS28") (pin "3") (pinfunction "DRAIN_3") (pintype "bidirectional"))
      (node (ref "R28") (pin "2") (pinfunction "2_2") (pintype "passive"))
    )
    (net (code "194") (name "Net-(MOS29-DRAIN)") (class "Default")
      (node (ref "MOS29") (pin "3") (pinfunction "DRAIN_3") (pintype "bidirectional"))
      (node (ref "R29") (pin "2") (pinfunction "2_2") (pintype "passive"))
    )
    (net (code "195") (name "Net-(MOS30-DRAIN)") (class "Default")
      (node (ref "MOS30") (pin "3") (pinfunction "DRAIN_3") (pintype "bidirectional"))
      (node (ref "R30") (pin "2") (pinfunction "2_2") (pintype "passive"))
    )
    (net (code "196") (name "Net-(MOS31-DRAIN)") (class "Default")
      (node (ref "MOS31") (pin "3") (pinfunction "DRAIN_3") (pintype "bidirectional"))
      (node (ref "R31") (pin "2") (pinfunction "2_2") (pintype "passive"))
    )
    (net (code "197") (name "Net-(MOS32-DRAIN)") (class "Default")
      (node (ref "MOS32") (pin "3") (pinfunction "DRAIN_3") (pintype "bidirectional"))
      (node (ref "R32") (pin "2") (pinfunction "2_2") (pintype "passive"))
    )
    (net (code "198") (name "Net-(MOS33-DRAIN)") (class "Default")
      (node (ref "MOS33") (pin "3") (pinfunction "DRAIN_3") (pintype "bidirectional"))
      (node (ref "R33") (pin "2") (pinfunction "2_2") (pintype "passive"))
    )
    (net (code "199") (name "Net-(MOS34-DRAIN)") (class "Default")
      (node (ref "MOS34") (pin "3") (pinfunction "DRAIN_3") (pintype "bidirectional"))
      (node (ref "R34") (pin "2") (pinfunction "2_2") (pintype "passive"))
    )
    (net (code "200") (name "Net-(MOS35-DRAIN)") (class "Default")
      (node (ref "MOS35") (pin "3") (pinfunction "DRAIN_3") (pintype "bidirectional"))
      (node (ref "R35") (pin "2") (pinfunction "2_2") (pintype "passive"))
    )
    (net (code "201") (name "Net-(MOS36-DRAIN)") (class "Default")
      (node (ref "MOS36") (pin "3") (pinfunction "DRAIN_3") (pintype "bidirectional"))
      (node (ref "R36") (pin "2") (pinfunction "2_2") (pintype "passive"))
    )
    (net (code "202") (name "Net-(MOS37-DRAIN)") (class "Default")
      (node (ref "MOS37") (pin "3") (pinfunction "DRAIN_3") (pintype "bidirectional"))
      (node (ref "R37") (pin "2") (pinfunction "2_2") (pintype "passive"))
    )
    (net (code "203") (name "Net-(MOS38-DRAIN)") (class "Default")
      (node (ref "MOS38") (pin "3") (pinfunction "DRAIN_3") (pintype "bidirectional"))
      (node (ref "R38") (pin "2") (pinfunction "2_2") (pintype "passive"))
    )
    (net (code "204") (name "Net-(MOS39-DRAIN)") (class "Default")
      (node (ref "MOS39") (pin "3") (pinfunction "DRAIN_3") (pintype "bidirectional"))
      (node (ref "R39") (pin "2") (pinfunction "2_2") (pintype "passive"))
    )
    (net (code "205") (name "Net-(MOS40-DRAIN)") (class "Default")
      (node (ref "MOS40") (pin "3") (pinfunction "DRAIN_3") (pintype "bidirectional"))
      (node (ref "R40") (pin "2") (pinfunction "2_2") (pintype "passive"))
    )
    (net (code "206") (name "Net-(MOS41-DRAIN)") (class "Default")
      (node (ref "MOS41") (pin "3") (pinfunction "DRAIN_3") (pintype "bidirectional"))
      (node (ref "R41") (pin "2") (pinfunction "2_2") (pintype "passive"))
    )
    (net (code "207") (name "Net-(MOS42-DRAIN)") (class "Default")
      (node (ref "MOS42") (pin "3") (pinfunction "DRAIN_3") (pintype "bidirectional"))
      (node (ref "R42") (pin "2") (pinfunction "2_2") (pintype "passive"))
    )
    (net (code "208") (name "Net-(MOS43-DRAIN)") (class "Default")
      (node (ref "MOS43") (pin "3") (pinfunction "DRAIN_3") (pintype "bidirectional"))
      (node (ref "R43") (pin "2") (pinfunction "2_2") (pintype "passive"))
    )
    (net (code "209") (name "Net-(MOS44-DRAIN)") (class "Default")
      (node (ref "MOS44") (pin "3") (pinfunction "DRAIN_3") (pintype "bidirectional"))
      (node (ref "R44") (pin "2") (pinfunction "2_2") (pintype "passive"))
    )
    (net (code "210") (name "Net-(MOS45-DRAIN)") (class "Default")
      (node (ref "MOS45") (pin "3") (pinfunction "DRAIN_3") (pintype "bidirectional"))
      (node (ref "R45") (pin "2") (pinfunction "2_2") (pintype "passive"))
    )
    (net (code "211") (name "Net-(MOS46-DRAIN)") (class "Default")
      (node (ref "MOS46") (pin "3") (pinfunction "DRAIN_3") (pintype "bidirectional"))
      (node (ref "R46") (pin "2") (pinfunction "2_2") (pintype "passive"))
    )
    (net (code "212") (name "Net-(MOS47-DRAIN)") (class "Default")
      (node (ref "MOS47") (pin "3") (pinfunction "DRAIN_3") (pintype "bidirectional"))
      (node (ref "R47") (pin "2") (pinfunction "2_2") (pintype "passive"))
    )
    (net (code "213") (name "Net-(MOS48-DRAIN)") (class "Default")
      (node (ref "MOS48") (pin "3") (pinfunction "DRAIN_3") (pintype "bidirectional"))
      (node (ref "R48") (pin "2") (pinfunction "2_2") (pintype "passive"))
    )
    (net (code "214") (name "Net-(MOS49-DRAIN)") (class "Default")
      (node (ref "MOS49") (pin "3") (pinfunction "DRAIN_3") (pintype "bidirectional"))
      (node (ref "R49") (pin "2") (pinfunction "2_2") (pintype "passive"))
    )
    (net (code "215") (name "Net-(MOS50-DRAIN)") (class "Default")
      (node (ref "MOS50") (pin "3") (pinfunction "DRAIN_3") (pintype "bidirectional"))
      (node (ref "R50") (pin "2") (pinfunction "2_2") (pintype "passive"))
    )
    (net (code "216") (name "Net-(MOS51-DRAIN)") (class "Default")
      (node (ref "MOS51") (pin "3") (pinfunction "DRAIN_3") (pintype "bidirectional"))
      (node (ref "R51") (pin "2") (pinfunction "2_2") (pintype "passive"))
    )
    (net (code "217") (name "Net-(MOS52-DRAIN)") (class "Default")
      (node (ref "MOS52") (pin "3") (pinfunction "DRAIN_3") (pintype "bidirectional"))
      (node (ref "R52") (pin "2") (pinfunction "2_2") (pintype "passive"))
    )
    (net (code "218") (name "Net-(MOS53-DRAIN)") (class "Default")
      (node (ref "MOS53") (pin "3") (pinfunction "DRAIN_3") (pintype "bidirectional"))
      (node (ref "R53") (pin "2") (pinfunction "2_2") (pintype "passive"))
    )
    (net (code "219") (name "Net-(MOS54-DRAIN)") (class "Default")
      (node (ref "MOS54") (pin "3") (pinfunction "DRAIN_3") (pintype "bidirectional"))
      (node (ref "R54") (pin "2") (pinfunction "2_2") (pintype "passive"))
    )
    (net (code "220") (name "Net-(MOS55-DRAIN)") (class "Default")
      (node (ref "MOS55") (pin "3") (pinfunction "DRAIN_3") (pintype "bidirectional"))
      (node (ref "R55") (pin "2") (pinfunction "2_2") (pintype "passive"))
    )
    (net (code "221") (name "Net-(MOS56-DRAIN)") (class "Default")
      (node (ref "MOS56") (pin "3") (pinfunction "DRAIN_3") (pintype "bidirectional"))
      (node (ref "R56") (pin "2") (pinfunction "2_2") (pintype "passive"))
    )
    (net (code "222") (name "Net-(MOS57-DRAIN)") (class "Default")
      (node (ref "MOS57") (pin "3") (pinfunction "DRAIN_3") (pintype "bidirectional"))
      (node (ref "R57") (pin "2") (pinfunction "2_2") (pintype "passive"))
    )
    (net (code "223") (name "Net-(MOS58-DRAIN)") (class "Default")
      (node (ref "MOS58") (pin "3") (pinfunction "DRAIN_3") (pintype "bidirectional"))
      (node (ref "R58") (pin "2") (pinfunction "2_2") (pintype "passive"))
    )
    (net (code "224") (name "Net-(MOS59-DRAIN)") (class "Default")
      (node (ref "MOS59") (pin "3") (pinfunction "DRAIN_3") (pintype "bidirectional"))
      (node (ref "R59") (pin "2") (pinfunction "2_2") (pintype "passive"))
    )
    (net (code "225") (name "Net-(MOS60-DRAIN)") (class "Default")
      (node (ref "MOS60") (pin "3") (pinfunction "DRAIN_3") (pintype "bidirectional"))
      (node (ref "R60") (pin "2") (pinfunction "2_2") (pintype "passive"))
    )
    (net (code "226") (name "Net-(MOS61-DRAIN)") (class "Default")
      (node (ref "MOS61") (pin "3") (pinfunction "DRAIN_3") (pintype "bidirectional"))
      (node (ref "R61") (pin "2") (pinfunction "2_2") (pintype "passive"))
    )
    (net (code "227") (name "Net-(MOS62-DRAIN)") (class "Default")
      (node (ref "MOS62") (pin "3") (pinfunction "DRAIN_3") (pintype "bidirectional"))
      (node (ref "R62") (pin "2") (pinfunction "2_2") (pintype "passive"))
    )
    (net (code "228") (name "Net-(MOS63-DRAIN)") (class "Default")
      (node (ref "MOS63") (pin "3") (pinfunction "DRAIN_3") (pintype "bidirectional"))
      (node (ref "R63") (pin "2") (pinfunction "2_2") (pintype "passive"))
    )
    (net (code "229") (name "Net-(MOS64-DRAIN)") (class "Default")
      (node (ref "MOS64") (pin "3") (pinfunction "DRAIN_3") (pintype "bidirectional"))
      (node (ref "R64") (pin "2") (pinfunction "2_2") (pintype "passive"))
    )
    (net (code "230") (name "Net-(MOS65-DRAIN)") (class "Default")
      (node (ref "MOS65") (pin "3") (pinfunction "DRAIN_3") (pintype "bidirectional"))
      (node (ref "R65") (pin "2") (pinfunction "2_2") (pintype "passive"))
    )
    (net (code "231") (name "Net-(MOS66-DRAIN)") (class "Default")
      (node (ref "MOS66") (pin "3") (pinfunction "DRAIN_3") (pintype "bidirectional"))
      (node (ref "R66") (pin "2") (pinfunction "2_2") (pintype "passive"))
    )
    (net (code "232") (name "Net-(MOS67-DRAIN)") (class "Default")
      (node (ref "MOS67") (pin "3") (pinfunction "DRAIN_3") (pintype "bidirectional"))
      (node (ref "R67") (pin "2") (pinfunction "2_2") (pintype "passive"))
    )
    (net (code "233") (name "Net-(MOS68-DRAIN)") (class "Default")
      (node (ref "MOS68") (pin "3") (pinfunction "DRAIN_3") (pintype "bidirectional"))
      (node (ref "R68") (pin "2") (pinfunction "2_2") (pintype "passive"))
    )
    (net (code "234") (name "Net-(MOS69-DRAIN)") (class "Default")
      (node (ref "MOS69") (pin "3") (pinfunction "DRAIN_3") (pintype "bidirectional"))
      (node (ref "R69") (pin "2") (pinfunction "2_2") (pintype "passive"))
    )
    (net (code "235") (name "Net-(MOS70-DRAIN)") (class "Default")
      (node (ref "MOS70") (pin "3") (pinfunction "DRAIN_3") (pintype "bidirectional"))
      (node (ref "R70") (pin "2") (pinfunction "2_2") (pintype "passive"))
    )
    (net (code "236") (name "Net-(MOS71-DRAIN)") (class "Default")
      (node (ref "MOS71") (pin "3") (pinfunction "DRAIN_3") (pintype "bidirectional"))
      (node (ref "R71") (pin "2") (pinfunction "2_2") (pintype "passive"))
    )
    (net (code "237") (name "Net-(MOS72-DRAIN)") (class "Default")
      (node (ref "MOS72") (pin "3") (pinfunction "DRAIN_3") (pintype "bidirectional"))
      (node (ref "R72") (pin "2") (pinfunction "2_2") (pintype "passive"))
    )
    (net (code "238") (name "Net-(MOS73-DRAIN)") (class "Default")
      (node (ref "MOS73") (pin "3") (pinfunction "DRAIN_3") (pintype "bidirectional"))
      (node (ref "R73") (pin "2") (pinfunction "2_2") (pintype "passive"))
    )
    (net (code "239") (name "Net-(MOS74-DRAIN)") (class "Default")
      (node (ref "MOS74") (pin "3") (pinfunction "DRAIN_3") (pintype "bidirectional"))
      (node (ref "R74") (pin "2") (pinfunction "2_2") (pintype "passive"))
    )
    (net (code "240") (name "Net-(MOS75-DRAIN)") (class "Default")
      (node (ref "MOS75") (pin "3") (pinfunction "DRAIN_3") (pintype "bidirectional"))
      (node (ref "R75") (pin "2") (pinfunction "2_2") (pintype "passive"))
    )
    (net (code "241") (name "Net-(MOS76-DRAIN)") (class "Default")
      (node (ref "MOS76") (pin "3") (pinfunction "DRAIN_3") (pintype "bidirectional"))
      (node (ref "R76") (pin "2") (pinfunction "2_2") (pintype "passive"))
    )
    (net (code "242") (name "Net-(MOS77-DRAIN)") (class "Default")
      (node (ref "MOS77") (pin "3") (pinfunction "DRAIN_3") (pintype "bidirectional"))
      (node (ref "R77") (pin "2") (pinfunction "2_2") (pintype "passive"))
    )
    (net (code "243") (name "Net-(MOS78-DRAIN)") (class "Default")
      (node (ref "MOS78") (pin "3") (pinfunction "DRAIN_3") (pintype "bidirectional"))
      (node (ref "R78") (pin "2") (pinfunction "2_2") (pintype "passive"))
    )
    (net (code "244") (name "Net-(MOS79-DRAIN)") (class "Default")
      (node (ref "MOS79") (pin "3") (pinfunction "DRAIN_3") (pintype "bidirectional"))
      (node (ref "R79") (pin "2") (pinfunction "2_2") (pintype "passive"))
    )
    (net (code "245") (name "Net-(MOS80-DRAIN)") (class "Default")
      (node (ref "MOS80") (pin "3") (pinfunction "DRAIN_3") (pintype "bidirectional"))
      (node (ref "R80") (pin "2") (pinfunction "2_2") (pintype "passive"))
    )
  )
)
